# motherboard_v1.net
KiCad netlist of a schematic drawn in EAGLE
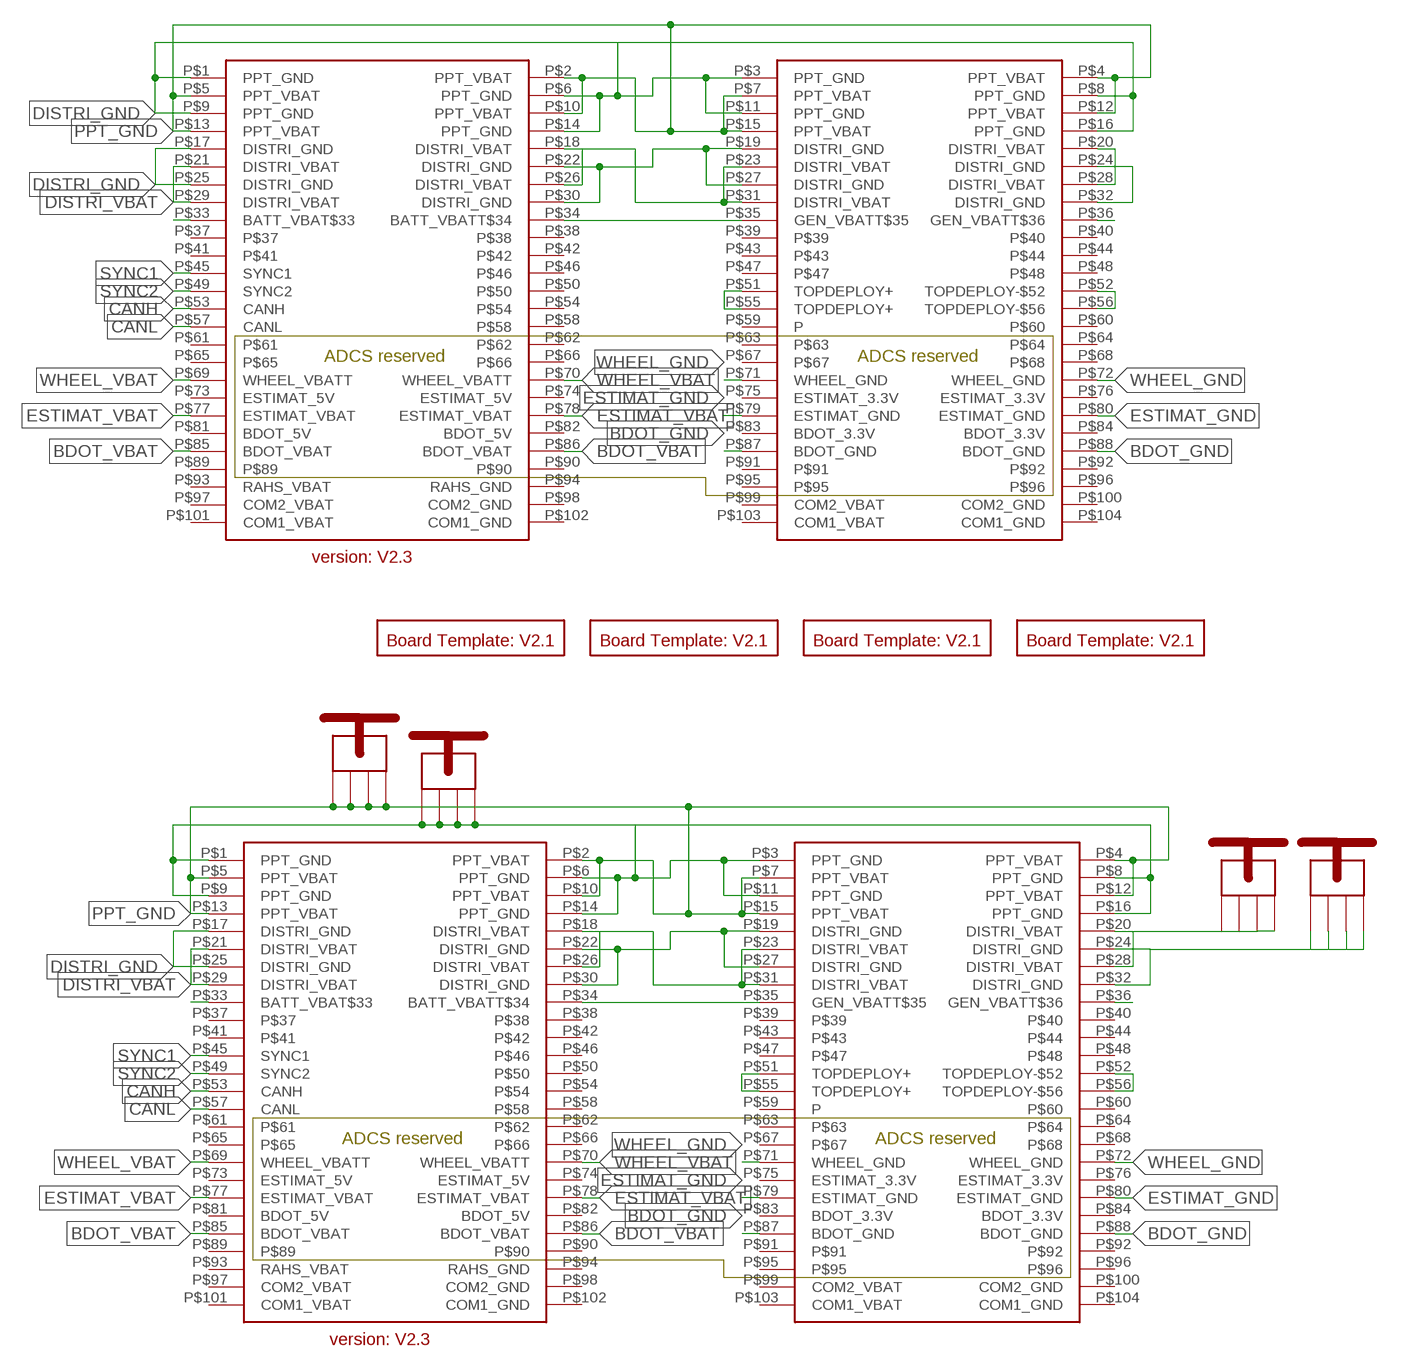
[diagram p0: schematic, sheet 1, part 1 of 2]
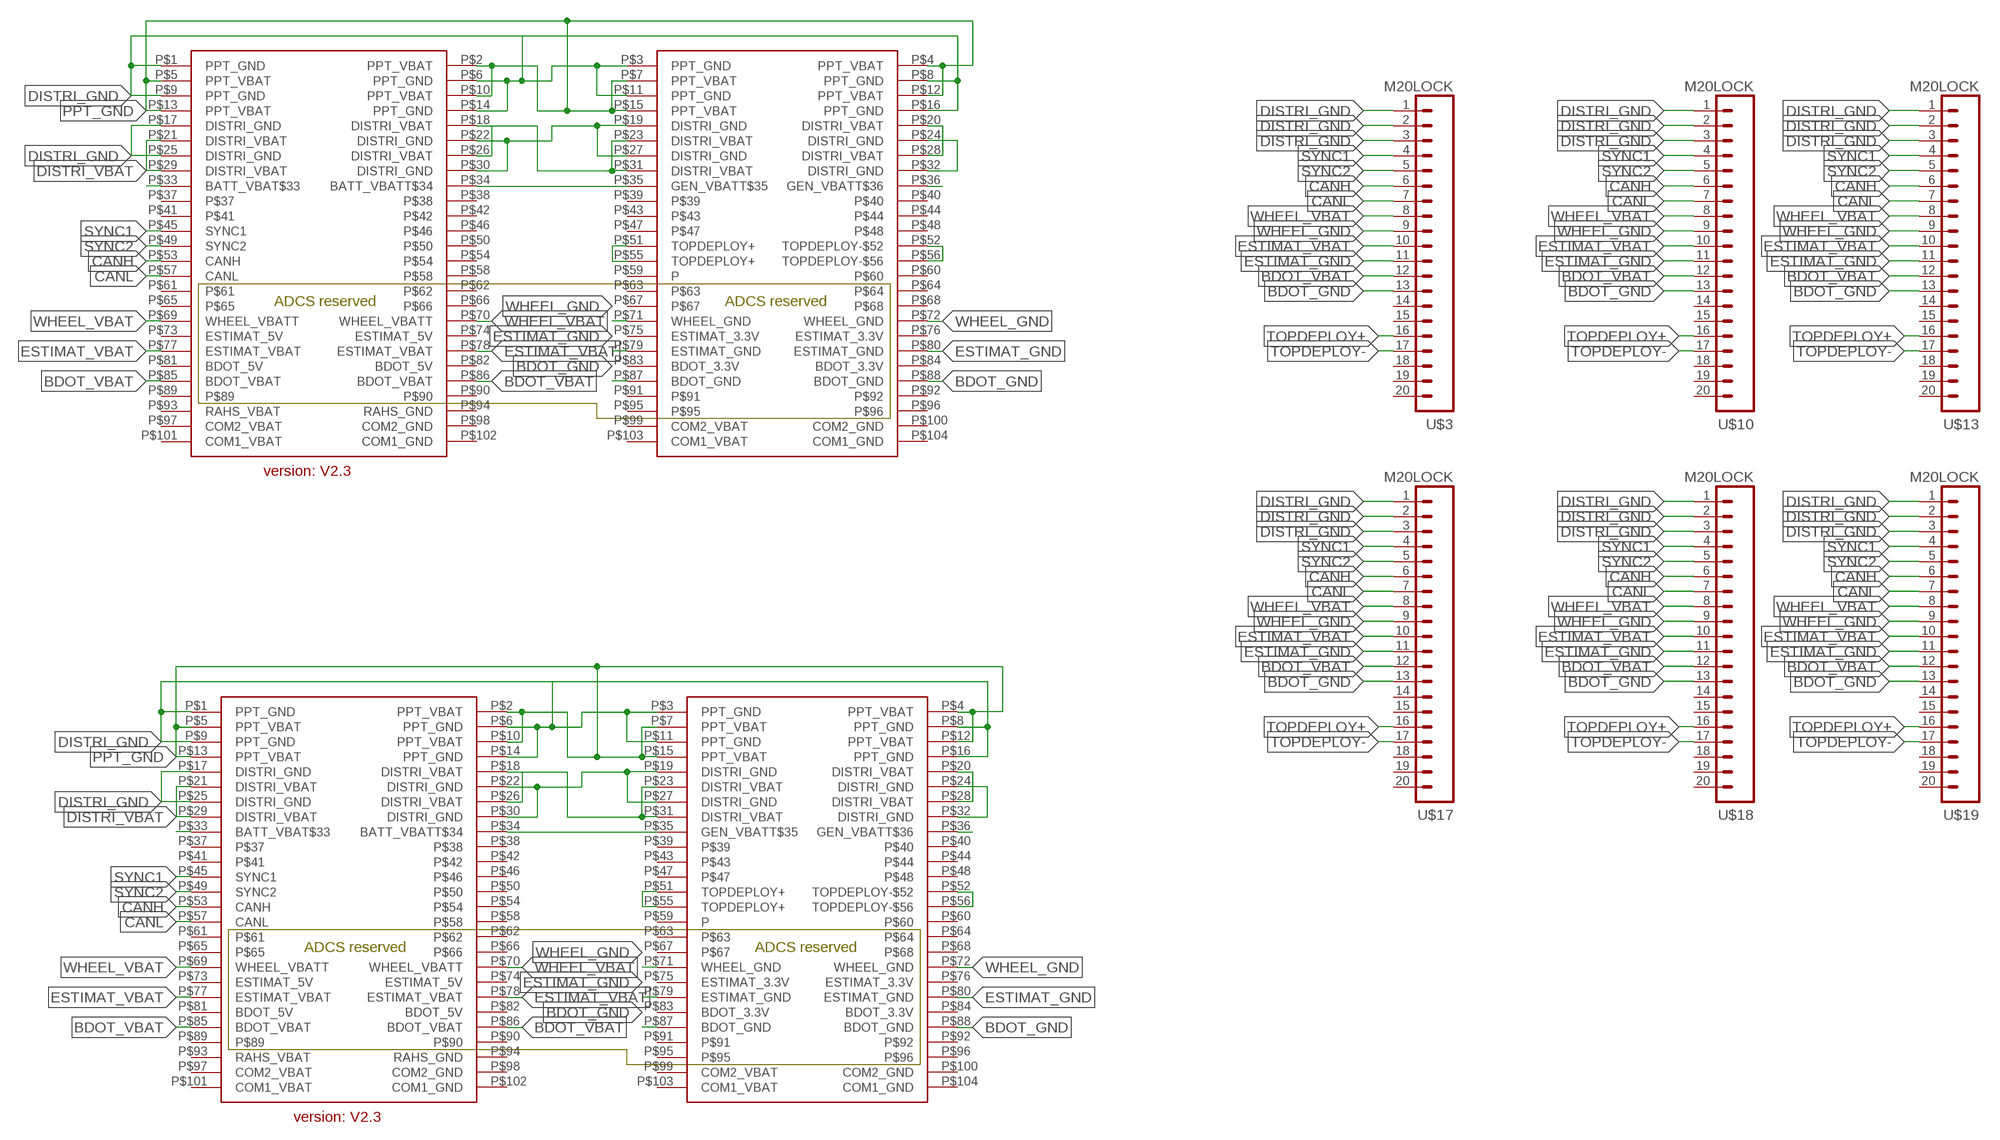
[diagram p1: schematic, sheet 1, part 2 of 2]

(export (version "E")
  (design (tool "Eeschema 10.0.6"))
  (components
    (comp (ref "JP1")
      (value "KEYSTONE_SCREW_TERMINAL_7701")
      (footprint "eagle-import:7701")
      (libsource (lib "eagle-import") (part "KEYSTONE_SCREW_TERMINAL_7701"))
    )
    (comp (ref "JP2")
      (value "KEYSTONE_SCREW_TERMINAL_7701")
      (footprint "eagle-import:7701")
      (libsource (lib "eagle-import") (part "KEYSTONE_SCREW_TERMINAL_7701"))
    )
    (comp (ref "JP9")
      (value "KEYSTONE_SCREW_TERMINAL_7701")
      (footprint "eagle-import:7701")
      (libsource (lib "eagle-import") (part "KEYSTONE_SCREW_TERMINAL_7701"))
    )
    (comp (ref "JP10")
      (value "KEYSTONE_SCREW_TERMINAL_7701")
      (footprint "eagle-import:7701")
      (libsource (lib "eagle-import") (part "KEYSTONE_SCREW_TERMINAL_7701"))
    )
    (comp (ref "U$1")
      (value "BOARD_TEMPLATESILKONLY")
      (footprint "eagle-import:BOARD_TEMPLATE_SILKONLY")
      (libsource (lib "eagle-import") (part "BOARD_TEMPLATESILKONLY"))
    )
    (comp (ref "U$2")
      (value "PC104_CONNECTOR")
      (footprint "eagle-import:PC104_CONNECTOR")
      (libsource (lib "eagle-import") (part "PC104_CONNECTOR"))
    )
    (comp (ref "U$3")
      (value "M20LOCK")
      (footprint "eagle-import:1X20_LOCK")
      (libsource (lib "eagle-import") (part "M20LOCK"))
    )
    (comp (ref "U$4")
      (value "BOARD_TEMPLATESILKONLY")
      (footprint "eagle-import:BOARD_TEMPLATE_SILKONLY")
      (libsource (lib "eagle-import") (part "BOARD_TEMPLATESILKONLY"))
    )
    (comp (ref "U$5")
      (value "BOARD_TEMPLATESILKONLY")
      (footprint "eagle-import:BOARD_TEMPLATE_SILKONLY")
      (libsource (lib "eagle-import") (part "BOARD_TEMPLATESILKONLY"))
    )
    (comp (ref "U$6")
      (value "BOARD_TEMPLATESILKONLY")
      (footprint "eagle-import:BOARD_TEMPLATE_SILKONLY")
      (libsource (lib "eagle-import") (part "BOARD_TEMPLATESILKONLY"))
    )
    (comp (ref "U$7")
      (value "PC104_CONNECTOR")
      (footprint "eagle-import:PC104_CONNECTOR")
      (libsource (lib "eagle-import") (part "PC104_CONNECTOR"))
    )
    (comp (ref "U$9")
      (value "PC104_CONNECTOR")
      (footprint "eagle-import:PC104_CONNECTOR")
      (libsource (lib "eagle-import") (part "PC104_CONNECTOR"))
    )
    (comp (ref "U$10")
      (value "M20LOCK")
      (footprint "eagle-import:1X20_LOCK")
      (libsource (lib "eagle-import") (part "M20LOCK"))
    )
    (comp (ref "U$11")
      (value "PC104_CONNECTOR")
      (footprint "eagle-import:PC104_CONNECTOR")
      (libsource (lib "eagle-import") (part "PC104_CONNECTOR"))
    )
    (comp (ref "U$13")
      (value "M20LOCK")
      (footprint "eagle-import:1X20_LOCK")
      (libsource (lib "eagle-import") (part "M20LOCK"))
    )
    (comp (ref "U$17")
      (value "M20LOCK")
      (footprint "eagle-import:1X20_LOCK")
      (libsource (lib "eagle-import") (part "M20LOCK"))
    )
    (comp (ref "U$18")
      (value "M20LOCK")
      (footprint "eagle-import:1X20_LOCK")
      (libsource (lib "eagle-import") (part "M20LOCK"))
    )
    (comp (ref "U$19")
      (value "M20LOCK")
      (footprint "eagle-import:1X20_LOCK")
      (libsource (lib "eagle-import") (part "M20LOCK"))
    )
  )
  (nets
    (net (code "1") (name "/EPS") (class "Default")
      (node (ref "U$11") (pin "P$33") (pinfunction "BATT_VBAT$33_P$33") (pintype "bidirectional"))
      (node (ref "U$11") (pin "P$34") (pinfunction "BATT_VBATT$34_P$34") (pintype "bidirectional"))
      (node (ref "U$11") (pin "P$35") (pinfunction "GEN_VBATT$35_P$35") (pintype "bidirectional"))
      (node (ref "U$11") (pin "P$36") (pinfunction "GEN_VBATT$36_P$36") (pintype "bidirectional"))
      (node (ref "U$2") (pin "P$33") (pinfunction "BATT_VBAT$33_P$33") (pintype "bidirectional"))
      (node (ref "U$2") (pin "P$34") (pinfunction "BATT_VBATT$34_P$34") (pintype "bidirectional"))
      (node (ref "U$2") (pin "P$35") (pinfunction "GEN_VBATT$35_P$35") (pintype "bidirectional"))
      (node (ref "U$2") (pin "P$36") (pinfunction "GEN_VBATT$36_P$36") (pintype "bidirectional"))
      (node (ref "U$7") (pin "P$33") (pinfunction "BATT_VBAT$33_P$33") (pintype "bidirectional"))
      (node (ref "U$7") (pin "P$34") (pinfunction "BATT_VBATT$34_P$34") (pintype "bidirectional"))
      (node (ref "U$7") (pin "P$35") (pinfunction "GEN_VBATT$35_P$35") (pintype "bidirectional"))
      (node (ref "U$7") (pin "P$36") (pinfunction "GEN_VBATT$36_P$36") (pintype "bidirectional"))
      (node (ref "U$9") (pin "P$33") (pinfunction "BATT_VBAT$33_P$33") (pintype "bidirectional"))
      (node (ref "U$9") (pin "P$34") (pinfunction "BATT_VBATT$34_P$34") (pintype "bidirectional"))
      (node (ref "U$9") (pin "P$35") (pinfunction "GEN_VBATT$35_P$35") (pintype "bidirectional"))
      (node (ref "U$9") (pin "P$36") (pinfunction "GEN_VBATT$36_P$36") (pintype "bidirectional"))
    )
    (net (code "2") (name "BDOT_GND") (class "Default")
      (node (ref "U$10") (pin "13") (pinfunction "13_13") (pintype "passive"))
      (node (ref "U$11") (pin "P$87") (pinfunction "BDOT_GND_P$87") (pintype "bidirectional"))
      (node (ref "U$11") (pin "P$88") (pinfunction "BDOT_GND_P$88") (pintype "bidirectional"))
      (node (ref "U$13") (pin "13") (pinfunction "13_13") (pintype "passive"))
      (node (ref "U$17") (pin "13") (pinfunction "13_13") (pintype "passive"))
      (node (ref "U$18") (pin "13") (pinfunction "13_13") (pintype "passive"))
      (node (ref "U$19") (pin "13") (pinfunction "13_13") (pintype "passive"))
      (node (ref "U$2") (pin "P$87") (pinfunction "BDOT_GND_P$87") (pintype "bidirectional"))
      (node (ref "U$2") (pin "P$88") (pinfunction "BDOT_GND_P$88") (pintype "bidirectional"))
      (node (ref "U$3") (pin "13") (pinfunction "13_13") (pintype "passive"))
      (node (ref "U$7") (pin "P$87") (pinfunction "BDOT_GND_P$87") (pintype "bidirectional"))
      (node (ref "U$7") (pin "P$88") (pinfunction "BDOT_GND_P$88") (pintype "bidirectional"))
      (node (ref "U$9") (pin "P$87") (pinfunction "BDOT_GND_P$87") (pintype "bidirectional"))
      (node (ref "U$9") (pin "P$88") (pinfunction "BDOT_GND_P$88") (pintype "bidirectional"))
    )
    (net (code "3") (name "BDOT_VBAT") (class "Default")
      (node (ref "U$10") (pin "12") (pinfunction "12_12") (pintype "passive"))
      (node (ref "U$11") (pin "P$85") (pinfunction "BDOT_VBAT_P$85") (pintype "bidirectional"))
      (node (ref "U$11") (pin "P$86") (pinfunction "BDOT_VBAT_P$86") (pintype "bidirectional"))
      (node (ref "U$13") (pin "12") (pinfunction "12_12") (pintype "passive"))
      (node (ref "U$17") (pin "12") (pinfunction "12_12") (pintype "passive"))
      (node (ref "U$18") (pin "12") (pinfunction "12_12") (pintype "passive"))
      (node (ref "U$19") (pin "12") (pinfunction "12_12") (pintype "passive"))
      (node (ref "U$2") (pin "P$85") (pinfunction "BDOT_VBAT_P$85") (pintype "bidirectional"))
      (node (ref "U$2") (pin "P$86") (pinfunction "BDOT_VBAT_P$86") (pintype "bidirectional"))
      (node (ref "U$3") (pin "12") (pinfunction "12_12") (pintype "passive"))
      (node (ref "U$7") (pin "P$85") (pinfunction "BDOT_VBAT_P$85") (pintype "bidirectional"))
      (node (ref "U$7") (pin "P$86") (pinfunction "BDOT_VBAT_P$86") (pintype "bidirectional"))
      (node (ref "U$9") (pin "P$85") (pinfunction "BDOT_VBAT_P$85") (pintype "bidirectional"))
      (node (ref "U$9") (pin "P$86") (pinfunction "BDOT_VBAT_P$86") (pintype "bidirectional"))
    )
    (net (code "4") (name "CANH") (class "Default")
      (node (ref "U$10") (pin "6") (pinfunction "6_6") (pintype "passive"))
      (node (ref "U$11") (pin "P$53") (pinfunction "CANH_P$53") (pintype "bidirectional"))
      (node (ref "U$13") (pin "6") (pinfunction "6_6") (pintype "passive"))
      (node (ref "U$17") (pin "6") (pinfunction "6_6") (pintype "passive"))
      (node (ref "U$18") (pin "6") (pinfunction "6_6") (pintype "passive"))
      (node (ref "U$19") (pin "6") (pinfunction "6_6") (pintype "passive"))
      (node (ref "U$2") (pin "P$53") (pinfunction "CANH_P$53") (pintype "bidirectional"))
      (node (ref "U$3") (pin "6") (pinfunction "6_6") (pintype "passive"))
      (node (ref "U$7") (pin "P$53") (pinfunction "CANH_P$53") (pintype "bidirectional"))
      (node (ref "U$9") (pin "P$53") (pinfunction "CANH_P$53") (pintype "bidirectional"))
    )
    (net (code "5") (name "CANL") (class "Default")
      (node (ref "U$10") (pin "7") (pinfunction "7_7") (pintype "passive"))
      (node (ref "U$11") (pin "P$57") (pinfunction "CANL_P$57") (pintype "bidirectional"))
      (node (ref "U$13") (pin "7") (pinfunction "7_7") (pintype "passive"))
      (node (ref "U$17") (pin "7") (pinfunction "7_7") (pintype "passive"))
      (node (ref "U$18") (pin "7") (pinfunction "7_7") (pintype "passive"))
      (node (ref "U$19") (pin "7") (pinfunction "7_7") (pintype "passive"))
      (node (ref "U$2") (pin "P$57") (pinfunction "CANL_P$57") (pintype "bidirectional"))
      (node (ref "U$3") (pin "7") (pinfunction "7_7") (pintype "passive"))
      (node (ref "U$7") (pin "P$57") (pinfunction "CANL_P$57") (pintype "bidirectional"))
      (node (ref "U$9") (pin "P$57") (pinfunction "CANL_P$57") (pintype "bidirectional"))
    )
    (net (code "6") (name "DISTRI_GND") (class "Default")
      (node (ref "JP10") (pin "P$1") (pinfunction "P$1_P$1") (pintype "bidirectional"))
      (node (ref "JP10") (pin "P$2") (pinfunction "P$2_P$2") (pintype "bidirectional"))
      (node (ref "JP10") (pin "P$3") (pinfunction "P$3_P$3") (pintype "bidirectional"))
      (node (ref "JP10") (pin "P$4") (pinfunction "P$4_P$4") (pintype "bidirectional"))
      (node (ref "JP2") (pin "P$1") (pinfunction "P$1_P$1") (pintype "bidirectional"))
      (node (ref "JP2") (pin "P$2") (pinfunction "P$2_P$2") (pintype "bidirectional"))
      (node (ref "JP2") (pin "P$3") (pinfunction "P$3_P$3") (pintype "bidirectional"))
      (node (ref "JP2") (pin "P$4") (pinfunction "P$4_P$4") (pintype "bidirectional"))
      (node (ref "U$10") (pin "1") (pinfunction "1_1") (pintype "passive"))
      (node (ref "U$10") (pin "2") (pinfunction "2_2") (pintype "passive"))
      (node (ref "U$10") (pin "3") (pinfunction "3_3") (pintype "passive"))
      (node (ref "U$11") (pin "P$1") (pinfunction "PPT_GND_P$1") (pintype "bidirectional"))
      (node (ref "U$11") (pin "P$11") (pinfunction "PPT_GND_P$11") (pintype "bidirectional"))
      (node (ref "U$11") (pin "P$14") (pinfunction "PPT_GND_P$14") (pintype "bidirectional"))
      (node (ref "U$11") (pin "P$16") (pinfunction "PPT_GND_P$16") (pintype "bidirectional"))
      (node (ref "U$11") (pin "P$17") (pinfunction "DISTRI_GND_P$17") (pintype "bidirectional"))
      (node (ref "U$11") (pin "P$19") (pinfunction "DISTRI_GND_P$19") (pintype "bidirectional"))
      (node (ref "U$11") (pin "P$22") (pinfunction "DISTRI_GND_P$22") (pintype "bidirectional"))
      (node (ref "U$11") (pin "P$24") (pinfunction "DISTRI_GND_P$24") (pintype "bidirectional"))
      (node (ref "U$11") (pin "P$25") (pinfunction "DISTRI_GND_P$25") (pintype "bidirectional"))
      (node (ref "U$11") (pin "P$27") (pinfunction "DISTRI_GND_P$27") (pintype "bidirectional"))
      (node (ref "U$11") (pin "P$3") (pinfunction "PPT_GND_P$3") (pintype "bidirectional"))
      (node (ref "U$11") (pin "P$30") (pinfunction "DISTRI_GND_P$30") (pintype "bidirectional"))
      (node (ref "U$11") (pin "P$32") (pinfunction "DISTRI_GND_P$32") (pintype "bidirectional"))
      (node (ref "U$11") (pin "P$6") (pinfunction "PPT_GND_P$6") (pintype "bidirectional"))
      (node (ref "U$11") (pin "P$8") (pinfunction "PPT_GND_P$8") (pintype "bidirectional"))
      (node (ref "U$11") (pin "P$9") (pinfunction "PPT_GND_P$9") (pintype "bidirectional"))
      (node (ref "U$13") (pin "1") (pinfunction "1_1") (pintype "passive"))
      (node (ref "U$13") (pin "2") (pinfunction "2_2") (pintype "passive"))
      (node (ref "U$13") (pin "3") (pinfunction "3_3") (pintype "passive"))
      (node (ref "U$17") (pin "1") (pinfunction "1_1") (pintype "passive"))
      (node (ref "U$17") (pin "2") (pinfunction "2_2") (pintype "passive"))
      (node (ref "U$17") (pin "3") (pinfunction "3_3") (pintype "passive"))
      (node (ref "U$18") (pin "1") (pinfunction "1_1") (pintype "passive"))
      (node (ref "U$18") (pin "2") (pinfunction "2_2") (pintype "passive"))
      (node (ref "U$18") (pin "3") (pinfunction "3_3") (pintype "passive"))
      (node (ref "U$19") (pin "1") (pinfunction "1_1") (pintype "passive"))
      (node (ref "U$19") (pin "2") (pinfunction "2_2") (pintype "passive"))
      (node (ref "U$19") (pin "3") (pinfunction "3_3") (pintype "passive"))
      (node (ref "U$2") (pin "P$1") (pinfunction "PPT_GND_P$1") (pintype "bidirectional"))
      (node (ref "U$2") (pin "P$11") (pinfunction "PPT_GND_P$11") (pintype "bidirectional"))
      (node (ref "U$2") (pin "P$14") (pinfunction "PPT_GND_P$14") (pintype "bidirectional"))
      (node (ref "U$2") (pin "P$16") (pinfunction "PPT_GND_P$16") (pintype "bidirectional"))
      (node (ref "U$2") (pin "P$17") (pinfunction "DISTRI_GND_P$17") (pintype "bidirectional"))
      (node (ref "U$2") (pin "P$19") (pinfunction "DISTRI_GND_P$19") (pintype "bidirectional"))
      (node (ref "U$2") (pin "P$22") (pinfunction "DISTRI_GND_P$22") (pintype "bidirectional"))
      (node (ref "U$2") (pin "P$24") (pinfunction "DISTRI_GND_P$24") (pintype "bidirectional"))
      (node (ref "U$2") (pin "P$25") (pinfunction "DISTRI_GND_P$25") (pintype "bidirectional"))
      (node (ref "U$2") (pin "P$27") (pinfunction "DISTRI_GND_P$27") (pintype "bidirectional"))
      (node (ref "U$2") (pin "P$3") (pinfunction "PPT_GND_P$3") (pintype "bidirectional"))
      (node (ref "U$2") (pin "P$30") (pinfunction "DISTRI_GND_P$30") (pintype "bidirectional"))
      (node (ref "U$2") (pin "P$32") (pinfunction "DISTRI_GND_P$32") (pintype "bidirectional"))
      (node (ref "U$2") (pin "P$6") (pinfunction "PPT_GND_P$6") (pintype "bidirectional"))
      (node (ref "U$2") (pin "P$8") (pinfunction "PPT_GND_P$8") (pintype "bidirectional"))
      (node (ref "U$2") (pin "P$9") (pinfunction "PPT_GND_P$9") (pintype "bidirectional"))
      (node (ref "U$3") (pin "1") (pinfunction "1_1") (pintype "passive"))
      (node (ref "U$3") (pin "2") (pinfunction "2_2") (pintype "passive"))
      (node (ref "U$3") (pin "3") (pinfunction "3_3") (pintype "passive"))
      (node (ref "U$7") (pin "P$1") (pinfunction "PPT_GND_P$1") (pintype "bidirectional"))
      (node (ref "U$7") (pin "P$11") (pinfunction "PPT_GND_P$11") (pintype "bidirectional"))
      (node (ref "U$7") (pin "P$14") (pinfunction "PPT_GND_P$14") (pintype "bidirectional"))
      (node (ref "U$7") (pin "P$16") (pinfunction "PPT_GND_P$16") (pintype "bidirectional"))
      (node (ref "U$7") (pin "P$17") (pinfunction "DISTRI_GND_P$17") (pintype "bidirectional"))
      (node (ref "U$7") (pin "P$19") (pinfunction "DISTRI_GND_P$19") (pintype "bidirectional"))
      (node (ref "U$7") (pin "P$22") (pinfunction "DISTRI_GND_P$22") (pintype "bidirectional"))
      (node (ref "U$7") (pin "P$24") (pinfunction "DISTRI_GND_P$24") (pintype "bidirectional"))
      (node (ref "U$7") (pin "P$25") (pinfunction "DISTRI_GND_P$25") (pintype "bidirectional"))
      (node (ref "U$7") (pin "P$27") (pinfunction "DISTRI_GND_P$27") (pintype "bidirectional"))
      (node (ref "U$7") (pin "P$3") (pinfunction "PPT_GND_P$3") (pintype "bidirectional"))
      (node (ref "U$7") (pin "P$30") (pinfunction "DISTRI_GND_P$30") (pintype "bidirectional"))
      (node (ref "U$7") (pin "P$32") (pinfunction "DISTRI_GND_P$32") (pintype "bidirectional"))
      (node (ref "U$7") (pin "P$6") (pinfunction "PPT_GND_P$6") (pintype "bidirectional"))
      (node (ref "U$7") (pin "P$8") (pinfunction "PPT_GND_P$8") (pintype "bidirectional"))
      (node (ref "U$7") (pin "P$9") (pinfunction "PPT_GND_P$9") (pintype "bidirectional"))
      (node (ref "U$9") (pin "P$1") (pinfunction "PPT_GND_P$1") (pintype "bidirectional"))
      (node (ref "U$9") (pin "P$11") (pinfunction "PPT_GND_P$11") (pintype "bidirectional"))
      (node (ref "U$9") (pin "P$14") (pinfunction "PPT_GND_P$14") (pintype "bidirectional"))
      (node (ref "U$9") (pin "P$16") (pinfunction "PPT_GND_P$16") (pintype "bidirectional"))
      (node (ref "U$9") (pin "P$17") (pinfunction "DISTRI_GND_P$17") (pintype "bidirectional"))
      (node (ref "U$9") (pin "P$19") (pinfunction "DISTRI_GND_P$19") (pintype "bidirectional"))
      (node (ref "U$9") (pin "P$22") (pinfunction "DISTRI_GND_P$22") (pintype "bidirectional"))
      (node (ref "U$9") (pin "P$24") (pinfunction "DISTRI_GND_P$24") (pintype "bidirectional"))
      (node (ref "U$9") (pin "P$25") (pinfunction "DISTRI_GND_P$25") (pintype "bidirectional"))
      (node (ref "U$9") (pin "P$27") (pinfunction "DISTRI_GND_P$27") (pintype "bidirectional"))
      (node (ref "U$9") (pin "P$3") (pinfunction "PPT_GND_P$3") (pintype "bidirectional"))
      (node (ref "U$9") (pin "P$30") (pinfunction "DISTRI_GND_P$30") (pintype "bidirectional"))
      (node (ref "U$9") (pin "P$32") (pinfunction "DISTRI_GND_P$32") (pintype "bidirectional"))
      (node (ref "U$9") (pin "P$6") (pinfunction "PPT_GND_P$6") (pintype "bidirectional"))
      (node (ref "U$9") (pin "P$8") (pinfunction "PPT_GND_P$8") (pintype "bidirectional"))
      (node (ref "U$9") (pin "P$9") (pinfunction "PPT_GND_P$9") (pintype "bidirectional"))
    )
    (net (code "7") (name "DISTRI_VBAT") (class "Default")
      (node (ref "JP1") (pin "P$1") (pinfunction "P$1_P$1") (pintype "bidirectional"))
      (node (ref "JP1") (pin "P$2") (pinfunction "P$2_P$2") (pintype "bidirectional"))
      (node (ref "JP1") (pin "P$3") (pinfunction "P$3_P$3") (pintype "bidirectional"))
      (node (ref "JP1") (pin "P$4") (pinfunction "P$4_P$4") (pintype "bidirectional"))
      (node (ref "U$11") (pin "P$18") (pinfunction "DISTRI_VBAT_P$18") (pintype "bidirectional"))
      (node (ref "U$11") (pin "P$20") (pinfunction "DISTRI_VBAT_P$20") (pintype "bidirectional"))
      (node (ref "U$11") (pin "P$21") (pinfunction "DISTRI_VBAT_P$21") (pintype "bidirectional"))
      (node (ref "U$11") (pin "P$23") (pinfunction "DISTRI_VBAT_P$23") (pintype "bidirectional"))
      (node (ref "U$11") (pin "P$26") (pinfunction "DISTRI_VBAT_P$26") (pintype "bidirectional"))
      (node (ref "U$11") (pin "P$28") (pinfunction "DISTRI_VBAT_P$28") (pintype "bidirectional"))
      (node (ref "U$11") (pin "P$29") (pinfunction "DISTRI_VBAT_P$29") (pintype "bidirectional"))
      (node (ref "U$11") (pin "P$31") (pinfunction "DISTRI_VBAT_P$31") (pintype "bidirectional"))
      (node (ref "U$2") (pin "P$18") (pinfunction "DISTRI_VBAT_P$18") (pintype "bidirectional"))
      (node (ref "U$2") (pin "P$20") (pinfunction "DISTRI_VBAT_P$20") (pintype "bidirectional"))
      (node (ref "U$2") (pin "P$21") (pinfunction "DISTRI_VBAT_P$21") (pintype "bidirectional"))
      (node (ref "U$2") (pin "P$23") (pinfunction "DISTRI_VBAT_P$23") (pintype "bidirectional"))
      (node (ref "U$2") (pin "P$26") (pinfunction "DISTRI_VBAT_P$26") (pintype "bidirectional"))
      (node (ref "U$2") (pin "P$28") (pinfunction "DISTRI_VBAT_P$28") (pintype "bidirectional"))
      (node (ref "U$2") (pin "P$29") (pinfunction "DISTRI_VBAT_P$29") (pintype "bidirectional"))
      (node (ref "U$2") (pin "P$31") (pinfunction "DISTRI_VBAT_P$31") (pintype "bidirectional"))
      (node (ref "U$7") (pin "P$18") (pinfunction "DISTRI_VBAT_P$18") (pintype "bidirectional"))
      (node (ref "U$7") (pin "P$20") (pinfunction "DISTRI_VBAT_P$20") (pintype "bidirectional"))
      (node (ref "U$7") (pin "P$21") (pinfunction "DISTRI_VBAT_P$21") (pintype "bidirectional"))
      (node (ref "U$7") (pin "P$23") (pinfunction "DISTRI_VBAT_P$23") (pintype "bidirectional"))
      (node (ref "U$7") (pin "P$26") (pinfunction "DISTRI_VBAT_P$26") (pintype "bidirectional"))
      (node (ref "U$7") (pin "P$28") (pinfunction "DISTRI_VBAT_P$28") (pintype "bidirectional"))
      (node (ref "U$7") (pin "P$29") (pinfunction "DISTRI_VBAT_P$29") (pintype "bidirectional"))
      (node (ref "U$7") (pin "P$31") (pinfunction "DISTRI_VBAT_P$31") (pintype "bidirectional"))
      (node (ref "U$9") (pin "P$18") (pinfunction "DISTRI_VBAT_P$18") (pintype "bidirectional"))
      (node (ref "U$9") (pin "P$20") (pinfunction "DISTRI_VBAT_P$20") (pintype "bidirectional"))
      (node (ref "U$9") (pin "P$21") (pinfunction "DISTRI_VBAT_P$21") (pintype "bidirectional"))
      (node (ref "U$9") (pin "P$23") (pinfunction "DISTRI_VBAT_P$23") (pintype "bidirectional"))
      (node (ref "U$9") (pin "P$26") (pinfunction "DISTRI_VBAT_P$26") (pintype "bidirectional"))
      (node (ref "U$9") (pin "P$28") (pinfunction "DISTRI_VBAT_P$28") (pintype "bidirectional"))
      (node (ref "U$9") (pin "P$29") (pinfunction "DISTRI_VBAT_P$29") (pintype "bidirectional"))
      (node (ref "U$9") (pin "P$31") (pinfunction "DISTRI_VBAT_P$31") (pintype "bidirectional"))
    )
    (net (code "8") (name "ESTIMAT_GND") (class "Default")
      (node (ref "U$10") (pin "11") (pinfunction "11_11") (pintype "passive"))
      (node (ref "U$11") (pin "P$79") (pinfunction "ESTIMAT_GND_P$79") (pintype "bidirectional"))
      (node (ref "U$11") (pin "P$80") (pinfunction "ESTIMAT_GND_P$80") (pintype "bidirectional"))
      (node (ref "U$13") (pin "11") (pinfunction "11_11") (pintype "passive"))
      (node (ref "U$17") (pin "11") (pinfunction "11_11") (pintype "passive"))
      (node (ref "U$18") (pin "11") (pinfunction "11_11") (pintype "passive"))
      (node (ref "U$19") (pin "11") (pinfunction "11_11") (pintype "passive"))
      (node (ref "U$2") (pin "P$79") (pinfunction "ESTIMAT_GND_P$79") (pintype "bidirectional"))
      (node (ref "U$2") (pin "P$80") (pinfunction "ESTIMAT_GND_P$80") (pintype "bidirectional"))
      (node (ref "U$3") (pin "11") (pinfunction "11_11") (pintype "passive"))
      (node (ref "U$7") (pin "P$79") (pinfunction "ESTIMAT_GND_P$79") (pintype "bidirectional"))
      (node (ref "U$7") (pin "P$80") (pinfunction "ESTIMAT_GND_P$80") (pintype "bidirectional"))
      (node (ref "U$9") (pin "P$79") (pinfunction "ESTIMAT_GND_P$79") (pintype "bidirectional"))
      (node (ref "U$9") (pin "P$80") (pinfunction "ESTIMAT_GND_P$80") (pintype "bidirectional"))
    )
    (net (code "9") (name "ESTIMAT_VBAT") (class "Default")
      (node (ref "U$10") (pin "10") (pinfunction "10_10") (pintype "passive"))
      (node (ref "U$11") (pin "P$77") (pinfunction "ESTIMAT_VBAT_P$77") (pintype "bidirectional"))
      (node (ref "U$11") (pin "P$78") (pinfunction "ESTIMAT_VBAT_P$78") (pintype "bidirectional"))
      (node (ref "U$13") (pin "10") (pinfunction "10_10") (pintype "passive"))
      (node (ref "U$17") (pin "10") (pinfunction "10_10") (pintype "passive"))
      (node (ref "U$18") (pin "10") (pinfunction "10_10") (pintype "passive"))
      (node (ref "U$19") (pin "10") (pinfunction "10_10") (pintype "passive"))
      (node (ref "U$2") (pin "P$77") (pinfunction "ESTIMAT_VBAT_P$77") (pintype "bidirectional"))
      (node (ref "U$2") (pin "P$78") (pinfunction "ESTIMAT_VBAT_P$78") (pintype "bidirectional"))
      (node (ref "U$3") (pin "10") (pinfunction "10_10") (pintype "passive"))
      (node (ref "U$7") (pin "P$77") (pinfunction "ESTIMAT_VBAT_P$77") (pintype "bidirectional"))
      (node (ref "U$7") (pin "P$78") (pinfunction "ESTIMAT_VBAT_P$78") (pintype "bidirectional"))
      (node (ref "U$9") (pin "P$77") (pinfunction "ESTIMAT_VBAT_P$77") (pintype "bidirectional"))
      (node (ref "U$9") (pin "P$78") (pinfunction "ESTIMAT_VBAT_P$78") (pintype "bidirectional"))
    )
    (net (code "10") (name "PPT_GND") (class "Default")
      (node (ref "JP9") (pin "P$1") (pinfunction "P$1_P$1") (pintype "bidirectional"))
      (node (ref "JP9") (pin "P$2") (pinfunction "P$2_P$2") (pintype "bidirectional"))
      (node (ref "JP9") (pin "P$3") (pinfunction "P$3_P$3") (pintype "bidirectional"))
      (node (ref "JP9") (pin "P$4") (pinfunction "P$4_P$4") (pintype "bidirectional"))
      (node (ref "U$11") (pin "P$10") (pinfunction "PPT_VBAT_P$10") (pintype "bidirectional"))
      (node (ref "U$11") (pin "P$12") (pinfunction "PPT_VBAT_P$12") (pintype "bidirectional"))
      (node (ref "U$11") (pin "P$13") (pinfunction "PPT_VBAT_P$13") (pintype "bidirectional"))
      (node (ref "U$11") (pin "P$15") (pinfunction "PPT_VBAT_P$15") (pintype "bidirectional"))
      (node (ref "U$11") (pin "P$2") (pinfunction "PPT_VBAT_P$2") (pintype "bidirectional"))
      (node (ref "U$11") (pin "P$4") (pinfunction "PPT_VBAT_P$4") (pintype "bidirectional"))
      (node (ref "U$11") (pin "P$5") (pinfunction "PPT_VBAT_P$5") (pintype "bidirectional"))
      (node (ref "U$11") (pin "P$7") (pinfunction "PPT_VBAT_P$7") (pintype "bidirectional"))
      (node (ref "U$2") (pin "P$10") (pinfunction "PPT_VBAT_P$10") (pintype "bidirectional"))
      (node (ref "U$2") (pin "P$12") (pinfunction "PPT_VBAT_P$12") (pintype "bidirectional"))
      (node (ref "U$2") (pin "P$13") (pinfunction "PPT_VBAT_P$13") (pintype "bidirectional"))
      (node (ref "U$2") (pin "P$15") (pinfunction "PPT_VBAT_P$15") (pintype "bidirectional"))
      (node (ref "U$2") (pin "P$2") (pinfunction "PPT_VBAT_P$2") (pintype "bidirectional"))
      (node (ref "U$2") (pin "P$4") (pinfunction "PPT_VBAT_P$4") (pintype "bidirectional"))
      (node (ref "U$2") (pin "P$5") (pinfunction "PPT_VBAT_P$5") (pintype "bidirectional"))
      (node (ref "U$2") (pin "P$7") (pinfunction "PPT_VBAT_P$7") (pintype "bidirectional"))
      (node (ref "U$7") (pin "P$10") (pinfunction "PPT_VBAT_P$10") (pintype "bidirectional"))
      (node (ref "U$7") (pin "P$12") (pinfunction "PPT_VBAT_P$12") (pintype "bidirectional"))
      (node (ref "U$7") (pin "P$13") (pinfunction "PPT_VBAT_P$13") (pintype "bidirectional"))
      (node (ref "U$7") (pin "P$15") (pinfunction "PPT_VBAT_P$15") (pintype "bidirectional"))
      (node (ref "U$7") (pin "P$2") (pinfunction "PPT_VBAT_P$2") (pintype "bidirectional"))
      (node (ref "U$7") (pin "P$4") (pinfunction "PPT_VBAT_P$4") (pintype "bidirectional"))
      (node (ref "U$7") (pin "P$5") (pinfunction "PPT_VBAT_P$5") (pintype "bidirectional"))
      (node (ref "U$7") (pin "P$7") (pinfunction "PPT_VBAT_P$7") (pintype "bidirectional"))
      (node (ref "U$9") (pin "P$10") (pinfunction "PPT_VBAT_P$10") (pintype "bidirectional"))
      (node (ref "U$9") (pin "P$12") (pinfunction "PPT_VBAT_P$12") (pintype "bidirectional"))
      (node (ref "U$9") (pin "P$13") (pinfunction "PPT_VBAT_P$13") (pintype "bidirectional"))
      (node (ref "U$9") (pin "P$15") (pinfunction "PPT_VBAT_P$15") (pintype "bidirectional"))
      (node (ref "U$9") (pin "P$2") (pinfunction "PPT_VBAT_P$2") (pintype "bidirectional"))
      (node (ref "U$9") (pin "P$4") (pinfunction "PPT_VBAT_P$4") (pintype "bidirectional"))
      (node (ref "U$9") (pin "P$5") (pinfunction "PPT_VBAT_P$5") (pintype "bidirectional"))
      (node (ref "U$9") (pin "P$7") (pinfunction "PPT_VBAT_P$7") (pintype "bidirectional"))
    )
    (net (code "11") (name "SYNC1") (class "Default")
      (node (ref "U$10") (pin "4") (pinfunction "4_4") (pintype "passive"))
      (node (ref "U$11") (pin "P$45") (pinfunction "SYNC1_P$45") (pintype "bidirectional"))
      (node (ref "U$13") (pin "4") (pinfunction "4_4") (pintype "passive"))
      (node (ref "U$17") (pin "4") (pinfunction "4_4") (pintype "passive"))
      (node (ref "U$18") (pin "4") (pinfunction "4_4") (pintype "passive"))
      (node (ref "U$19") (pin "4") (pinfunction "4_4") (pintype "passive"))
      (node (ref "U$2") (pin "P$45") (pinfunction "SYNC1_P$45") (pintype "bidirectional"))
      (node (ref "U$3") (pin "4") (pinfunction "4_4") (pintype "passive"))
      (node (ref "U$7") (pin "P$45") (pinfunction "SYNC1_P$45") (pintype "bidirectional"))
      (node (ref "U$9") (pin "P$45") (pinfunction "SYNC1_P$45") (pintype "bidirectional"))
    )
    (net (code "12") (name "SYNC2") (class "Default")
      (node (ref "U$10") (pin "5") (pinfunction "5_5") (pintype "passive"))
      (node (ref "U$11") (pin "P$49") (pinfunction "SYNC2_P$49") (pintype "bidirectional"))
      (node (ref "U$13") (pin "5") (pinfunction "5_5") (pintype "passive"))
      (node (ref "U$17") (pin "5") (pinfunction "5_5") (pintype "passive"))
      (node (ref "U$18") (pin "5") (pinfunction "5_5") (pintype "passive"))
      (node (ref "U$19") (pin "5") (pinfunction "5_5") (pintype "passive"))
      (node (ref "U$2") (pin "P$49") (pinfunction "SYNC2_P$49") (pintype "bidirectional"))
      (node (ref "U$3") (pin "5") (pinfunction "5_5") (pintype "passive"))
      (node (ref "U$7") (pin "P$49") (pinfunction "SYNC2_P$49") (pintype "bidirectional"))
      (node (ref "U$9") (pin "P$49") (pinfunction "SYNC2_P$49") (pintype "bidirectional"))
    )
    (net (code "13") (name "TOPDEPLOY+") (class "Default")
      (node (ref "U$10") (pin "16") (pinfunction "16_16") (pintype "passive"))
      (node (ref "U$11") (pin "P$51") (pinfunction "TOPDEPLOY+_P$51") (pintype "bidirectional"))
      (node (ref "U$11") (pin "P$55") (pinfunction "TOPDEPLOY+_P$55") (pintype "bidirectional"))
      (node (ref "U$13") (pin "16") (pinfunction "16_16") (pintype "passive"))
      (node (ref "U$17") (pin "16") (pinfunction "16_16") (pintype "passive"))
      (node (ref "U$18") (pin "16") (pinfunction "16_16") (pintype "passive"))
      (node (ref "U$19") (pin "16") (pinfunction "16_16") (pintype "passive"))
      (node (ref "U$2") (pin "P$51") (pinfunction "TOPDEPLOY+_P$51") (pintype "bidirectional"))
      (node (ref "U$2") (pin "P$55") (pinfunction "TOPDEPLOY+_P$55") (pintype "bidirectional"))
      (node (ref "U$3") (pin "16") (pinfunction "16_16") (pintype "passive"))
      (node (ref "U$7") (pin "P$51") (pinfunction "TOPDEPLOY+_P$51") (pintype "bidirectional"))
      (node (ref "U$7") (pin "P$55") (pinfunction "TOPDEPLOY+_P$55") (pintype "bidirectional"))
      (node (ref "U$9") (pin "P$51") (pinfunction "TOPDEPLOY+_P$51") (pintype "bidirectional"))
      (node (ref "U$9") (pin "P$55") (pinfunction "TOPDEPLOY+_P$55") (pintype "bidirectional"))
    )
    (net (code "14") (name "TOPDEPLOY-") (class "Default")
      (node (ref "U$10") (pin "17") (pinfunction "17_17") (pintype "passive"))
      (node (ref "U$11") (pin "P$52") (pinfunction "TOPDEPLOY-$52_P$52") (pintype "bidirectional"))
      (node (ref "U$11") (pin "P$56") (pinfunction "TOPDEPLOY-$56_P$56") (pintype "bidirectional"))
      (node (ref "U$13") (pin "17") (pinfunction "17_17") (pintype "passive"))
      (node (ref "U$17") (pin "17") (pinfunction "17_17") (pintype "passive"))
      (node (ref "U$18") (pin "17") (pinfunction "17_17") (pintype "passive"))
      (node (ref "U$19") (pin "17") (pinfunction "17_17") (pintype "passive"))
      (node (ref "U$2") (pin "P$52") (pinfunction "TOPDEPLOY-$52_P$52") (pintype "bidirectional"))
      (node (ref "U$2") (pin "P$56") (pinfunction "TOPDEPLOY-$56_P$56") (pintype "bidirectional"))
      (node (ref "U$3") (pin "17") (pinfunction "17_17") (pintype "passive"))
      (node (ref "U$7") (pin "P$52") (pinfunction "TOPDEPLOY-$52_P$52") (pintype "bidirectional"))
      (node (ref "U$7") (pin "P$56") (pinfunction "TOPDEPLOY-$56_P$56") (pintype "bidirectional"))
      (node (ref "U$9") (pin "P$52") (pinfunction "TOPDEPLOY-$52_P$52") (pintype "bidirectional"))
      (node (ref "U$9") (pin "P$56") (pinfunction "TOPDEPLOY-$56_P$56") (pintype "bidirectional"))
    )
    (net (code "15") (name "WHEEL_GND") (class "Default")
      (node (ref "U$10") (pin "9") (pinfunction "9_9") (pintype "passive"))
      (node (ref "U$11") (pin "P$71") (pinfunction "WHEEL_GND_P$71") (pintype "bidirectional"))
      (node (ref "U$11") (pin "P$72") (pinfunction "WHEEL_GND_P$72") (pintype "bidirectional"))
      (node (ref "U$13") (pin "9") (pinfunction "9_9") (pintype "passive"))
      (node (ref "U$17") (pin "9") (pinfunction "9_9") (pintype "passive"))
      (node (ref "U$18") (pin "9") (pinfunction "9_9") (pintype "passive"))
      (node (ref "U$19") (pin "9") (pinfunction "9_9") (pintype "passive"))
      (node (ref "U$2") (pin "P$71") (pinfunction "WHEEL_GND_P$71") (pintype "bidirectional"))
      (node (ref "U$2") (pin "P$72") (pinfunction "WHEEL_GND_P$72") (pintype "bidirectional"))
      (node (ref "U$3") (pin "9") (pinfunction "9_9") (pintype "passive"))
      (node (ref "U$7") (pin "P$71") (pinfunction "WHEEL_GND_P$71") (pintype "bidirectional"))
      (node (ref "U$7") (pin "P$72") (pinfunction "WHEEL_GND_P$72") (pintype "bidirectional"))
      (node (ref "U$9") (pin "P$71") (pinfunction "WHEEL_GND_P$71") (pintype "bidirectional"))
      (node (ref "U$9") (pin "P$72") (pinfunction "WHEEL_GND_P$72") (pintype "bidirectional"))
    )
    (net (code "16") (name "WHEEL_VBAT") (class "Default")
      (node (ref "U$10") (pin "8") (pinfunction "8_8") (pintype "passive"))
      (node (ref "U$11") (pin "P$69") (pinfunction "WHEEL_VBATT_P$69") (pintype "bidirectional"))
      (node (ref "U$11") (pin "P$70") (pinfunction "WHEEL_VBATT_P$70") (pintype "bidirectional"))
      (node (ref "U$13") (pin "8") (pinfunction "8_8") (pintype "passive"))
      (node (ref "U$17") (pin "8") (pinfunction "8_8") (pintype "passive"))
      (node (ref "U$18") (pin "8") (pinfunction "8_8") (pintype "passive"))
      (node (ref "U$19") (pin "8") (pinfunction "8_8") (pintype "passive"))
      (node (ref "U$2") (pin "P$69") (pinfunction "WHEEL_VBATT_P$69") (pintype "bidirectional"))
      (node (ref "U$2") (pin "P$70") (pinfunction "WHEEL_VBATT_P$70") (pintype "bidirectional"))
      (node (ref "U$3") (pin "8") (pinfunction "8_8") (pintype "passive"))
      (node (ref "U$7") (pin "P$69") (pinfunction "WHEEL_VBATT_P$69") (pintype "bidirectional"))
      (node (ref "U$7") (pin "P$70") (pinfunction "WHEEL_VBATT_P$70") (pintype "bidirectional"))
      (node (ref "U$9") (pin "P$69") (pinfunction "WHEEL_VBATT_P$69") (pintype "bidirectional"))
      (node (ref "U$9") (pin "P$70") (pinfunction "WHEEL_VBATT_P$70") (pintype "bidirectional"))
    )
    (net (code "17") (name "unconnected-(U$2-BDOT_3.3V-PadP$83)") (class "Default")
      (node (ref "U$2") (pin "P$83") (pinfunction "BDOT_3.3V_P$83") (pintype "bidirectional"))
    )
    (net (code "18") (name "unconnected-(U$2-BDOT_3.3V-PadP$84)") (class "Default")
      (node (ref "U$2") (pin "P$84") (pinfunction "BDOT_3.3V_P$84") (pintype "bidirectional"))
    )
    (net (code "19") (name "unconnected-(U$2-BDOT_5V-PadP$81)") (class "Default")
      (node (ref "U$2") (pin "P$81") (pinfunction "BDOT_5V_P$81") (pintype "bidirectional"))
    )
    (net (code "20") (name "unconnected-(U$2-BDOT_5V-PadP$82)") (class "Default")
      (node (ref "U$2") (pin "P$82") (pinfunction "BDOT_5V_P$82") (pintype "bidirectional"))
    )
    (net (code "21") (name "unconnected-(U$2-COM1_GND-PadP$102)") (class "Default")
      (node (ref "U$2") (pin "P$102") (pinfunction "COM1_GND_P$102") (pintype "bidirectional"))
    )
    (net (code "22") (name "unconnected-(U$2-COM1_GND-PadP$104)") (class "Default")
      (node (ref "U$2") (pin "P$104") (pinfunction "COM1_GND_P$104") (pintype "bidirectional"))
    )
    (net (code "23") (name "unconnected-(U$2-COM1_VBAT-PadP$101)") (class "Default")
      (node (ref "U$2") (pin "P$101") (pinfunction "COM1_VBAT_P$101") (pintype "bidirectional"))
    )
    (net (code "24") (name "unconnected-(U$2-COM1_VBAT-PadP$103)") (class "Default")
      (node (ref "U$2") (pin "P$103") (pinfunction "COM1_VBAT_P$103") (pintype "bidirectional"))
    )
    (net (code "25") (name "unconnected-(U$2-COM2_GND-PadP$98)") (class "Default")
      (node (ref "U$2") (pin "P$98") (pinfunction "COM2_GND_P$98") (pintype "bidirectional"))
    )
    (net (code "26") (name "unconnected-(U$2-COM2_GND-PadP$100)") (class "Default")
      (node (ref "U$2") (pin "P$100") (pinfunction "COM2_GND_P$100") (pintype "bidirectional"))
    )
    (net (code "27") (name "unconnected-(U$2-COM2_VBAT-PadP$97)") (class "Default")
      (node (ref "U$2") (pin "P$97") (pinfunction "COM2_VBAT_P$97") (pintype "bidirectional"))
    )
    (net (code "28") (name "unconnected-(U$2-COM2_VBAT-PadP$99)") (class "Default")
      (node (ref "U$2") (pin "P$99") (pinfunction "COM2_VBAT_P$99") (pintype "bidirectional"))
    )
    (net (code "29") (name "unconnected-(U$2-ESTIMAT_3.3V-PadP$75)") (class "Default")
      (node (ref "U$2") (pin "P$75") (pinfunction "ESTIMAT_3.3V_P$75") (pintype "bidirectional"))
    )
    (net (code "30") (name "unconnected-(U$2-ESTIMAT_3.3V-PadP$76)") (class "Default")
      (node (ref "U$2") (pin "P$76") (pinfunction "ESTIMAT_3.3V_P$76") (pintype "bidirectional"))
    )
    (net (code "31") (name "unconnected-(U$2-ESTIMAT_5V-PadP$73)") (class "Default")
      (node (ref "U$2") (pin "P$73") (pinfunction "ESTIMAT_5V_P$73") (pintype "bidirectional"))
    )
    (net (code "32") (name "unconnected-(U$2-ESTIMAT_5V-PadP$74)") (class "Default")
      (node (ref "U$2") (pin "P$74") (pinfunction "ESTIMAT_5V_P$74") (pintype "bidirectional"))
    )
    (net (code "33") (name "unconnected-(U$2-P-PadP$59)") (class "Default")
      (node (ref "U$2") (pin "P$59") (pinfunction "P_P$59") (pintype "bidirectional"))
    )
    (net (code "34") (name "unconnected-(U$2-PadP$37)") (class "Default")
      (node (ref "U$2") (pin "P$37") (pinfunction "P$37_P$37") (pintype "bidirectional"))
    )
    (net (code "35") (name "unconnected-(U$2-PadP$38)") (class "Default")
      (node (ref "U$2") (pin "P$38") (pinfunction "P$38_P$38") (pintype "bidirectional"))
    )
    (net (code "36") (name "unconnected-(U$2-PadP$39)") (class "Default")
      (node (ref "U$2") (pin "P$39") (pinfunction "P$39_P$39") (pintype "bidirectional"))
    )
    (net (code "37") (name "unconnected-(U$2-PadP$40)") (class "Default")
      (node (ref "U$2") (pin "P$40") (pinfunction "P$40_P$40") (pintype "bidirectional"))
    )
    (net (code "38") (name "unconnected-(U$2-PadP$41)") (class "Default")
      (node (ref "U$2") (pin "P$41") (pinfunction "P$41_P$41") (pintype "bidirectional"))
    )
    (net (code "39") (name "unconnected-(U$2-PadP$42)") (class "Default")
      (node (ref "U$2") (pin "P$42") (pinfunction "P$42_P$42") (pintype "bidirectional"))
    )
    (net (code "40") (name "unconnected-(U$2-PadP$43)") (class "Default")
      (node (ref "U$2") (pin "P$43") (pinfunction "P$43_P$43") (pintype "bidirectional"))
    )
    (net (code "41") (name "unconnected-(U$2-PadP$44)") (class "Default")
      (node (ref "U$2") (pin "P$44") (pinfunction "P$44_P$44") (pintype "bidirectional"))
    )
    (net (code "42") (name "unconnected-(U$2-PadP$46)") (class "Default")
      (node (ref "U$2") (pin "P$46") (pinfunction "P$46_P$46") (pintype "bidirectional"))
    )
    (net (code "43") (name "unconnected-(U$2-PadP$47)") (class "Default")
      (node (ref "U$2") (pin "P$47") (pinfunction "P$47_P$47") (pintype "bidirectional"))
    )
    (net (code "44") (name "unconnected-(U$2-PadP$48)") (class "Default")
      (node (ref "U$2") (pin "P$48") (pinfunction "P$48_P$48") (pintype "bidirectional"))
    )
    (net (code "45") (name "unconnected-(U$2-PadP$50)") (class "Default")
      (node (ref "U$2") (pin "P$50") (pinfunction "P$50_P$50") (pintype "bidirectional"))
    )
    (net (code "46") (name "unconnected-(U$2-PadP$54)") (class "Default")
      (node (ref "U$2") (pin "P$54") (pinfunction "P$54_P$54") (pintype "bidirectional"))
    )
    (net (code "47") (name "unconnected-(U$2-PadP$58)") (class "Default")
      (node (ref "U$2") (pin "P$58") (pinfunction "P$58_P$58") (pintype "bidirectional"))
    )
    (net (code "48") (name "unconnected-(U$2-PadP$60)") (class "Default")
      (node (ref "U$2") (pin "P$60") (pinfunction "P$60_P$60") (pintype "bidirectional"))
    )
    (net (code "49") (name "unconnected-(U$2-PadP$61)") (class "Default")
      (node (ref "U$2") (pin "P$61") (pinfunction "P$61_P$61") (pintype "bidirectional"))
    )
    (net (code "50") (name "unconnected-(U$2-PadP$62)") (class "Default")
      (node (ref "U$2") (pin "P$62") (pinfunction "P$62_P$62") (pintype "bidirectional"))
    )
    (net (code "51") (name "unconnected-(U$2-PadP$63)") (class "Default")
      (node (ref "U$2") (pin "P$63") (pinfunction "P$63_P$63") (pintype "bidirectional"))
    )
    (net (code "52") (name "unconnected-(U$2-PadP$64)") (class "Default")
      (node (ref "U$2") (pin "P$64") (pinfunction "P$64_P$64") (pintype "bidirectional"))
    )
    (net (code "53") (name "unconnected-(U$2-PadP$65)") (class "Default")
      (node (ref "U$2") (pin "P$65") (pinfunction "P$65_P$65") (pintype "bidirectional"))
    )
    (net (code "54") (name "unconnected-(U$2-PadP$66)") (class "Default")
      (node (ref "U$2") (pin "P$66") (pinfunction "P$66_P$66") (pintype "bidirectional"))
    )
    (net (code "55") (name "unconnected-(U$2-PadP$67)") (class "Default")
      (node (ref "U$2") (pin "P$67") (pinfunction "P$67_P$67") (pintype "bidirectional"))
    )
    (net (code "56") (name "unconnected-(U$2-PadP$68)") (class "Default")
      (node (ref "U$2") (pin "P$68") (pinfunction "P$68_P$68") (pintype "bidirectional"))
    )
    (net (code "57") (name "unconnected-(U$2-PadP$89)") (class "Default")
      (node (ref "U$2") (pin "P$89") (pinfunction "P$89_P$89") (pintype "bidirectional"))
    )
    (net (code "58") (name "unconnected-(U$2-PadP$90)") (class "Default")
      (node (ref "U$2") (pin "P$90") (pinfunction "P$90_P$90") (pintype "bidirectional"))
    )
    (net (code "59") (name "unconnected-(U$2-PadP$91)") (class "Default")
      (node (ref "U$2") (pin "P$91") (pinfunction "P$91_P$91") (pintype "bidirectional"))
    )
    (net (code "60") (name "unconnected-(U$2-PadP$92)") (class "Default")
      (node (ref "U$2") (pin "P$92") (pinfunction "P$92_P$92") (pintype "bidirectional"))
    )
    (net (code "61") (name "unconnected-(U$2-PadP$95)") (class "Default")
      (node (ref "U$2") (pin "P$95") (pinfunction "P$95_P$95") (pintype "bidirectional"))
    )
    (net (code "62") (name "unconnected-(U$2-PadP$96)") (class "Default")
      (node (ref "U$2") (pin "P$96") (pinfunction "P$96_P$96") (pintype "bidirectional"))
    )
    (net (code "63") (name "unconnected-(U$2-RAHS_GND-PadP$94)") (class "Default")
      (node (ref "U$2") (pin "P$94") (pinfunction "RAHS_GND_P$94") (pintype "bidirectional"))
    )
    (net (code "64") (name "unconnected-(U$2-RAHS_VBAT-PadP$93)") (class "Default")
      (node (ref "U$2") (pin "P$93") (pinfunction "RAHS_VBAT_P$93") (pintype "bidirectional"))
    )
    (net (code "65") (name "unconnected-(U$3-Pad14)") (class "Default")
      (node (ref "U$3") (pin "14") (pinfunction "14_14") (pintype "passive"))
    )
    (net (code "66") (name "unconnected-(U$3-Pad15)") (class "Default")
      (node (ref "U$3") (pin "15") (pinfunction "15_15") (pintype "passive"))
    )
    (net (code "67") (name "unconnected-(U$3-Pad18)") (class "Default")
      (node (ref "U$3") (pin "18") (pinfunction "18_18") (pintype "passive"))
    )
    (net (code "68") (name "unconnected-(U$3-Pad19)") (class "Default")
      (node (ref "U$3") (pin "19") (pinfunction "19_19") (pintype "passive"))
    )
    (net (code "69") (name "unconnected-(U$3-Pad20)") (class "Default")
      (node (ref "U$3") (pin "20") (pinfunction "20_20") (pintype "passive"))
    )
    (net (code "70") (name "unconnected-(U$7-BDOT_3.3V-PadP$83)") (class "Default")
      (node (ref "U$7") (pin "P$83") (pinfunction "BDOT_3.3V_P$83") (pintype "bidirectional"))
    )
    (net (code "71") (name "unconnected-(U$7-BDOT_3.3V-PadP$84)") (class "Default")
      (node (ref "U$7") (pin "P$84") (pinfunction "BDOT_3.3V_P$84") (pintype "bidirectional"))
    )
    (net (code "72") (name "unconnected-(U$7-BDOT_5V-PadP$81)") (class "Default")
      (node (ref "U$7") (pin "P$81") (pinfunction "BDOT_5V_P$81") (pintype "bidirectional"))
    )
    (net (code "73") (name "unconnected-(U$7-BDOT_5V-PadP$82)") (class "Default")
      (node (ref "U$7") (pin "P$82") (pinfunction "BDOT_5V_P$82") (pintype "bidirectional"))
    )
    (net (code "74") (name "unconnected-(U$7-COM1_GND-PadP$102)") (class "Default")
      (node (ref "U$7") (pin "P$102") (pinfunction "COM1_GND_P$102") (pintype "bidirectional"))
    )
    (net (code "75") (name "unconnected-(U$7-COM1_GND-PadP$104)") (class "Default")
      (node (ref "U$7") (pin "P$104") (pinfunction "COM1_GND_P$104") (pintype "bidirectional"))
    )
    (net (code "76") (name "unconnected-(U$7-COM1_VBAT-PadP$101)") (class "Default")
      (node (ref "U$7") (pin "P$101") (pinfunction "COM1_VBAT_P$101") (pintype "bidirectional"))
    )
    (net (code "77") (name "unconnected-(U$7-COM1_VBAT-PadP$103)") (class "Default")
      (node (ref "U$7") (pin "P$103") (pinfunction "COM1_VBAT_P$103") (pintype "bidirectional"))
    )
    (net (code "78") (name "unconnected-(U$7-COM2_GND-PadP$98)") (class "Default")
      (node (ref "U$7") (pin "P$98") (pinfunction "COM2_GND_P$98") (pintype "bidirectional"))
    )
    (net (code "79") (name "unconnected-(U$7-COM2_GND-PadP$100)") (class "Default")
      (node (ref "U$7") (pin "P$100") (pinfunction "COM2_GND_P$100") (pintype "bidirectional"))
    )
    (net (code "80") (name "unconnected-(U$7-COM2_VBAT-PadP$97)") (class "Default")
      (node (ref "U$7") (pin "P$97") (pinfunction "COM2_VBAT_P$97") (pintype "bidirectional"))
    )
    (net (code "81") (name "unconnected-(U$7-COM2_VBAT-PadP$99)") (class "Default")
      (node (ref "U$7") (pin "P$99") (pinfunction "COM2_VBAT_P$99") (pintype "bidirectional"))
    )
    (net (code "82") (name "unconnected-(U$7-ESTIMAT_3.3V-PadP$75)") (class "Default")
      (node (ref "U$7") (pin "P$75") (pinfunction "ESTIMAT_3.3V_P$75") (pintype "bidirectional"))
    )
    (net (code "83") (name "unconnected-(U$7-ESTIMAT_3.3V-PadP$76)") (class "Default")
      (node (ref "U$7") (pin "P$76") (pinfunction "ESTIMAT_3.3V_P$76") (pintype "bidirectional"))
    )
    (net (code "84") (name "unconnected-(U$7-ESTIMAT_5V-PadP$73)") (class "Default")
      (node (ref "U$7") (pin "P$73") (pinfunction "ESTIMAT_5V_P$73") (pintype "bidirectional"))
    )
    (net (code "85") (name "unconnected-(U$7-ESTIMAT_5V-PadP$74)") (class "Default")
      (node (ref "U$7") (pin "P$74") (pinfunction "ESTIMAT_5V_P$74") (pintype "bidirectional"))
    )
    (net (code "86") (name "unconnected-(U$7-P-PadP$59)") (class "Default")
      (node (ref "U$7") (pin "P$59") (pinfunction "P_P$59") (pintype "bidirectional"))
    )
    (net (code "87") (name "unconnected-(U$7-PadP$37)") (class "Default")
      (node (ref "U$7") (pin "P$37") (pinfunction "P$37_P$37") (pintype "bidirectional"))
    )
    (net (code "88") (name "unconnected-(U$7-PadP$38)") (class "Default")
      (node (ref "U$7") (pin "P$38") (pinfunction "P$38_P$38") (pintype "bidirectional"))
    )
    (net (code "89") (name "unconnected-(U$7-PadP$39)") (class "Default")
      (node (ref "U$7") (pin "P$39") (pinfunction "P$39_P$39") (pintype "bidirectional"))
    )
    (net (code "90") (name "unconnected-(U$7-PadP$40)") (class "Default")
      (node (ref "U$7") (pin "P$40") (pinfunction "P$40_P$40") (pintype "bidirectional"))
    )
    (net (code "91") (name "unconnected-(U$7-PadP$41)") (class "Default")
      (node (ref "U$7") (pin "P$41") (pinfunction "P$41_P$41") (pintype "bidirectional"))
    )
    (net (code "92") (name "unconnected-(U$7-PadP$42)") (class "Default")
      (node (ref "U$7") (pin "P$42") (pinfunction "P$42_P$42") (pintype "bidirectional"))
    )
    (net (code "93") (name "unconnected-(U$7-PadP$43)") (class "Default")
      (node (ref "U$7") (pin "P$43") (pinfunction "P$43_P$43") (pintype "bidirectional"))
    )
    (net (code "94") (name "unconnected-(U$7-PadP$44)") (class "Default")
      (node (ref "U$7") (pin "P$44") (pinfunction "P$44_P$44") (pintype "bidirectional"))
    )
    (net (code "95") (name "unconnected-(U$7-PadP$46)") (class "Default")
      (node (ref "U$7") (pin "P$46") (pinfunction "P$46_P$46") (pintype "bidirectional"))
    )
    (net (code "96") (name "unconnected-(U$7-PadP$47)") (class "Default")
      (node (ref "U$7") (pin "P$47") (pinfunction "P$47_P$47") (pintype "bidirectional"))
    )
    (net (code "97") (name "unconnected-(U$7-PadP$48)") (class "Default")
      (node (ref "U$7") (pin "P$48") (pinfunction "P$48_P$48") (pintype "bidirectional"))
    )
    (net (code "98") (name "unconnected-(U$7-PadP$50)") (class "Default")
      (node (ref "U$7") (pin "P$50") (pinfunction "P$50_P$50") (pintype "bidirectional"))
    )
    (net (code "99") (name "unconnected-(U$7-PadP$54)") (class "Default")
      (node (ref "U$7") (pin "P$54") (pinfunction "P$54_P$54") (pintype "bidirectional"))
    )
    (net (code "100") (name "unconnected-(U$7-PadP$58)") (class "Default")
      (node (ref "U$7") (pin "P$58") (pinfunction "P$58_P$58") (pintype "bidirectional"))
    )
    (net (code "101") (name "unconnected-(U$7-PadP$60)") (class "Default")
      (node (ref "U$7") (pin "P$60") (pinfunction "P$60_P$60") (pintype "bidirectional"))
    )
    (net (code "102") (name "unconnected-(U$7-PadP$61)") (class "Default")
      (node (ref "U$7") (pin "P$61") (pinfunction "P$61_P$61") (pintype "bidirectional"))
    )
    (net (code "103") (name "unconnected-(U$7-PadP$62)") (class "Default")
      (node (ref "U$7") (pin "P$62") (pinfunction "P$62_P$62") (pintype "bidirectional"))
    )
    (net (code "104") (name "unconnected-(U$7-PadP$63)") (class "Default")
      (node (ref "U$7") (pin "P$63") (pinfunction "P$63_P$63") (pintype "bidirectional"))
    )
    (net (code "105") (name "unconnected-(U$7-PadP$64)") (class "Default")
      (node (ref "U$7") (pin "P$64") (pinfunction "P$64_P$64") (pintype "bidirectional"))
    )
    (net (code "106") (name "unconnected-(U$7-PadP$65)") (class "Default")
      (node (ref "U$7") (pin "P$65") (pinfunction "P$65_P$65") (pintype "bidirectional"))
    )
    (net (code "107") (name "unconnected-(U$7-PadP$66)") (class "Default")
      (node (ref "U$7") (pin "P$66") (pinfunction "P$66_P$66") (pintype "bidirectional"))
    )
    (net (code "108") (name "unconnected-(U$7-PadP$67)") (class "Default")
      (node (ref "U$7") (pin "P$67") (pinfunction "P$67_P$67") (pintype "bidirectional"))
    )
    (net (code "109") (name "unconnected-(U$7-PadP$68)") (class "Default")
      (node (ref "U$7") (pin "P$68") (pinfunction "P$68_P$68") (pintype "bidirectional"))
    )
    (net (code "110") (name "unconnected-(U$7-PadP$89)") (class "Default")
      (node (ref "U$7") (pin "P$89") (pinfunction "P$89_P$89") (pintype "bidirectional"))
    )
    (net (code "111") (name "unconnected-(U$7-PadP$90)") (class "Default")
      (node (ref "U$7") (pin "P$90") (pinfunction "P$90_P$90") (pintype "bidirectional"))
    )
    (net (code "112") (name "unconnected-(U$7-PadP$91)") (class "Default")
      (node (ref "U$7") (pin "P$91") (pinfunction "P$91_P$91") (pintype "bidirectional"))
    )
    (net (code "113") (name "unconnected-(U$7-PadP$92)") (class "Default")
      (node (ref "U$7") (pin "P$92") (pinfunction "P$92_P$92") (pintype "bidirectional"))
    )
    (net (code "114") (name "unconnected-(U$7-PadP$95)") (class "Default")
      (node (ref "U$7") (pin "P$95") (pinfunction "P$95_P$95") (pintype "bidirectional"))
    )
    (net (code "115") (name "unconnected-(U$7-PadP$96)") (class "Default")
      (node (ref "U$7") (pin "P$96") (pinfunction "P$96_P$96") (pintype "bidirectional"))
    )
    (net (code "116") (name "unconnected-(U$7-RAHS_GND-PadP$94)") (class "Default")
      (node (ref "U$7") (pin "P$94") (pinfunction "RAHS_GND_P$94") (pintype "bidirectional"))
    )
    (net (code "117") (name "unconnected-(U$7-RAHS_VBAT-PadP$93)") (class "Default")
      (node (ref "U$7") (pin "P$93") (pinfunction "RAHS_VBAT_P$93") (pintype "bidirectional"))
    )
    (net (code "118") (name "unconnected-(U$9-BDOT_3.3V-PadP$83)") (class "Default")
      (node (ref "U$9") (pin "P$83") (pinfunction "BDOT_3.3V_P$83") (pintype "bidirectional"))
    )
    (net (code "119") (name "unconnected-(U$9-BDOT_3.3V-PadP$84)") (class "Default")
      (node (ref "U$9") (pin "P$84") (pinfunction "BDOT_3.3V_P$84") (pintype "bidirectional"))
    )
    (net (code "120") (name "unconnected-(U$9-BDOT_5V-PadP$81)") (class "Default")
      (node (ref "U$9") (pin "P$81") (pinfunction "BDOT_5V_P$81") (pintype "bidirectional"))
    )
    (net (code "121") (name "unconnected-(U$9-BDOT_5V-PadP$82)") (class "Default")
      (node (ref "U$9") (pin "P$82") (pinfunction "BDOT_5V_P$82") (pintype "bidirectional"))
    )
    (net (code "122") (name "unconnected-(U$9-COM1_GND-PadP$102)") (class "Default")
      (node (ref "U$9") (pin "P$102") (pinfunction "COM1_GND_P$102") (pintype "bidirectional"))
    )
    (net (code "123") (name "unconnected-(U$9-COM1_GND-PadP$104)") (class "Default")
      (node (ref "U$9") (pin "P$104") (pinfunction "COM1_GND_P$104") (pintype "bidirectional"))
    )
    (net (code "124") (name "unconnected-(U$9-COM1_VBAT-PadP$101)") (class "Default")
      (node (ref "U$9") (pin "P$101") (pinfunction "COM1_VBAT_P$101") (pintype "bidirectional"))
    )
    (net (code "125") (name "unconnected-(U$9-COM1_VBAT-PadP$103)") (class "Default")
      (node (ref "U$9") (pin "P$103") (pinfunction "COM1_VBAT_P$103") (pintype "bidirectional"))
    )
    (net (code "126") (name "unconnected-(U$9-COM2_GND-PadP$98)") (class "Default")
      (node (ref "U$9") (pin "P$98") (pinfunction "COM2_GND_P$98") (pintype "bidirectional"))
    )
    (net (code "127") (name "unconnected-(U$9-COM2_GND-PadP$100)") (class "Default")
      (node (ref "U$9") (pin "P$100") (pinfunction "COM2_GND_P$100") (pintype "bidirectional"))
    )
    (net (code "128") (name "unconnected-(U$9-COM2_VBAT-PadP$97)") (class "Default")
      (node (ref "U$9") (pin "P$97") (pinfunction "COM2_VBAT_P$97") (pintype "bidirectional"))
    )
    (net (code "129") (name "unconnected-(U$9-COM2_VBAT-PadP$99)") (class "Default")
      (node (ref "U$9") (pin "P$99") (pinfunction "COM2_VBAT_P$99") (pintype "bidirectional"))
    )
    (net (code "130") (name "unconnected-(U$9-ESTIMAT_3.3V-PadP$75)") (class "Default")
      (node (ref "U$9") (pin "P$75") (pinfunction "ESTIMAT_3.3V_P$75") (pintype "bidirectional"))
    )
    (net (code "131") (name "unconnected-(U$9-ESTIMAT_3.3V-PadP$76)") (class "Default")
      (node (ref "U$9") (pin "P$76") (pinfunction "ESTIMAT_3.3V_P$76") (pintype "bidirectional"))
    )
    (net (code "132") (name "unconnected-(U$9-ESTIMAT_5V-PadP$73)") (class "Default")
      (node (ref "U$9") (pin "P$73") (pinfunction "ESTIMAT_5V_P$73") (pintype "bidirectional"))
    )
    (net (code "133") (name "unconnected-(U$9-ESTIMAT_5V-PadP$74)") (class "Default")
      (node (ref "U$9") (pin "P$74") (pinfunction "ESTIMAT_5V_P$74") (pintype "bidirectional"))
    )
    (net (code "134") (name "unconnected-(U$9-P-PadP$59)") (class "Default")
      (node (ref "U$9") (pin "P$59") (pinfunction "P_P$59") (pintype "bidirectional"))
    )
    (net (code "135") (name "unconnected-(U$9-PadP$37)") (class "Default")
      (node (ref "U$9") (pin "P$37") (pinfunction "P$37_P$37") (pintype "bidirectional"))
    )
    (net (code "136") (name "unconnected-(U$9-PadP$38)") (class "Default")
      (node (ref "U$9") (pin "P$38") (pinfunction "P$38_P$38") (pintype "bidirectional"))
    )
    (net (code "137") (name "unconnected-(U$9-PadP$39)") (class "Default")
      (node (ref "U$9") (pin "P$39") (pinfunction "P$39_P$39") (pintype "bidirectional"))
    )
    (net (code "138") (name "unconnected-(U$9-PadP$40)") (class "Default")
      (node (ref "U$9") (pin "P$40") (pinfunction "P$40_P$40") (pintype "bidirectional"))
    )
    (net (code "139") (name "unconnected-(U$9-PadP$41)") (class "Default")
      (node (ref "U$9") (pin "P$41") (pinfunction "P$41_P$41") (pintype "bidirectional"))
    )
    (net (code "140") (name "unconnected-(U$9-PadP$42)") (class "Default")
      (node (ref "U$9") (pin "P$42") (pinfunction "P$42_P$42") (pintype "bidirectional"))
    )
    (net (code "141") (name "unconnected-(U$9-PadP$43)") (class "Default")
      (node (ref "U$9") (pin "P$43") (pinfunction "P$43_P$43") (pintype "bidirectional"))
    )
    (net (code "142") (name "unconnected-(U$9-PadP$44)") (class "Default")
      (node (ref "U$9") (pin "P$44") (pinfunction "P$44_P$44") (pintype "bidirectional"))
    )
    (net (code "143") (name "unconnected-(U$9-PadP$46)") (class "Default")
      (node (ref "U$9") (pin "P$46") (pinfunction "P$46_P$46") (pintype "bidirectional"))
    )
    (net (code "144") (name "unconnected-(U$9-PadP$47)") (class "Default")
      (node (ref "U$9") (pin "P$47") (pinfunction "P$47_P$47") (pintype "bidirectional"))
    )
    (net (code "145") (name "unconnected-(U$9-PadP$48)") (class "Default")
      (node (ref "U$9") (pin "P$48") (pinfunction "P$48_P$48") (pintype "bidirectional"))
    )
    (net (code "146") (name "unconnected-(U$9-PadP$50)") (class "Default")
      (node (ref "U$9") (pin "P$50") (pinfunction "P$50_P$50") (pintype "bidirectional"))
    )
    (net (code "147") (name "unconnected-(U$9-PadP$54)") (class "Default")
      (node (ref "U$9") (pin "P$54") (pinfunction "P$54_P$54") (pintype "bidirectional"))
    )
    (net (code "148") (name "unconnected-(U$9-PadP$58)") (class "Default")
      (node (ref "U$9") (pin "P$58") (pinfunction "P$58_P$58") (pintype "bidirectional"))
    )
    (net (code "149") (name "unconnected-(U$9-PadP$60)") (class "Default")
      (node (ref "U$9") (pin "P$60") (pinfunction "P$60_P$60") (pintype "bidirectional"))
    )
    (net (code "150") (name "unconnected-(U$9-PadP$61)") (class "Default")
      (node (ref "U$9") (pin "P$61") (pinfunction "P$61_P$61") (pintype "bidirectional"))
    )
    (net (code "151") (name "unconnected-(U$9-PadP$62)") (class "Default")
      (node (ref "U$9") (pin "P$62") (pinfunction "P$62_P$62") (pintype "bidirectional"))
    )
    (net (code "152") (name "unconnected-(U$9-PadP$63)") (class "Default")
      (node (ref "U$9") (pin "P$63") (pinfunction "P$63_P$63") (pintype "bidirectional"))
    )
    (net (code "153") (name "unconnected-(U$9-PadP$64)") (class "Default")
      (node (ref "U$9") (pin "P$64") (pinfunction "P$64_P$64") (pintype "bidirectional"))
    )
    (net (code "154") (name "unconnected-(U$9-PadP$65)") (class "Default")
      (node (ref "U$9") (pin "P$65") (pinfunction "P$65_P$65") (pintype "bidirectional"))
    )
    (net (code "155") (name "unconnected-(U$9-PadP$66)") (class "Default")
      (node (ref "U$9") (pin "P$66") (pinfunction "P$66_P$66") (pintype "bidirectional"))
    )
    (net (code "156") (name "unconnected-(U$9-PadP$67)") (class "Default")
      (node (ref "U$9") (pin "P$67") (pinfunction "P$67_P$67") (pintype "bidirectional"))
    )
    (net (code "157") (name "unconnected-(U$9-PadP$68)") (class "Default")
      (node (ref "U$9") (pin "P$68") (pinfunction "P$68_P$68") (pintype "bidirectional"))
    )
    (net (code "158") (name "unconnected-(U$9-PadP$89)") (class "Default")
      (node (ref "U$9") (pin "P$89") (pinfunction "P$89_P$89") (pintype "bidirectional"))
    )
    (net (code "159") (name "unconnected-(U$9-PadP$90)") (class "Default")
      (node (ref "U$9") (pin "P$90") (pinfunction "P$90_P$90") (pintype "bidirectional"))
    )
    (net (code "160") (name "unconnected-(U$9-PadP$91)") (class "Default")
      (node (ref "U$9") (pin "P$91") (pinfunction "P$91_P$91") (pintype "bidirectional"))
    )
    (net (code "161") (name "unconnected-(U$9-PadP$92)") (class "Default")
      (node (ref "U$9") (pin "P$92") (pinfunction "P$92_P$92") (pintype "bidirectional"))
    )
    (net (code "162") (name "unconnected-(U$9-PadP$95)") (class "Default")
      (node (ref "U$9") (pin "P$95") (pinfunction "P$95_P$95") (pintype "bidirectional"))
    )
    (net (code "163") (name "unconnected-(U$9-PadP$96)") (class "Default")
      (node (ref "U$9") (pin "P$96") (pinfunction "P$96_P$96") (pintype "bidirectional"))
    )
    (net (code "164") (name "unconnected-(U$9-RAHS_GND-PadP$94)") (class "Default")
      (node (ref "U$9") (pin "P$94") (pinfunction "RAHS_GND_P$94") (pintype "bidirectional"))
    )
    (net (code "165") (name "unconnected-(U$9-RAHS_VBAT-PadP$93)") (class "Default")
      (node (ref "U$9") (pin "P$93") (pinfunction "RAHS_VBAT_P$93") (pintype "bidirectional"))
    )
    (net (code "166") (name "unconnected-(U$10-Pad14)") (class "Default")
      (node (ref "U$10") (pin "14") (pinfunction "14_14") (pintype "passive"))
    )
    (net (code "167") (name "unconnected-(U$10-Pad15)") (class "Default")
      (node (ref "U$10") (pin "15") (pinfunction "15_15") (pintype "passive"))
    )
    (net (code "168") (name "unconnected-(U$10-Pad18)") (class "Default")
      (node (ref "U$10") (pin "18") (pinfunction "18_18") (pintype "passive"))
    )
    (net (code "169") (name "unconnected-(U$10-Pad19)") (class "Default")
      (node (ref "U$10") (pin "19") (pinfunction "19_19") (pintype "passive"))
    )
    (net (code "170") (name "unconnected-(U$10-Pad20)") (class "Default")
      (node (ref "U$10") (pin "20") (pinfunction "20_20") (pintype "passive"))
    )
    (net (code "171") (name "unconnected-(U$11-BDOT_3.3V-PadP$83)") (class "Default")
      (node (ref "U$11") (pin "P$83") (pinfunction "BDOT_3.3V_P$83") (pintype "bidirectional"))
    )
    (net (code "172") (name "unconnected-(U$11-BDOT_3.3V-PadP$84)") (class "Default")
      (node (ref "U$11") (pin "P$84") (pinfunction "BDOT_3.3V_P$84") (pintype "bidirectional"))
    )
    (net (code "173") (name "unconnected-(U$11-BDOT_5V-PadP$81)") (class "Default")
      (node (ref "U$11") (pin "P$81") (pinfunction "BDOT_5V_P$81") (pintype "bidirectional"))
    )
    (net (code "174") (name "unconnected-(U$11-BDOT_5V-PadP$82)") (class "Default")
      (node (ref "U$11") (pin "P$82") (pinfunction "BDOT_5V_P$82") (pintype "bidirectional"))
    )
    (net (code "175") (name "unconnected-(U$11-COM1_GND-PadP$102)") (class "Default")
      (node (ref "U$11") (pin "P$102") (pinfunction "COM1_GND_P$102") (pintype "bidirectional"))
    )
    (net (code "176") (name "unconnected-(U$11-COM1_GND-PadP$104)") (class "Default")
      (node (ref "U$11") (pin "P$104") (pinfunction "COM1_GND_P$104") (pintype "bidirectional"))
    )
    (net (code "177") (name "unconnected-(U$11-COM1_VBAT-PadP$101)") (class "Default")
      (node (ref "U$11") (pin "P$101") (pinfunction "COM1_VBAT_P$101") (pintype "bidirectional"))
    )
    (net (code "178") (name "unconnected-(U$11-COM1_VBAT-PadP$103)") (class "Default")
      (node (ref "U$11") (pin "P$103") (pinfunction "COM1_VBAT_P$103") (pintype "bidirectional"))
    )
    (net (code "179") (name "unconnected-(U$11-COM2_GND-PadP$98)") (class "Default")
      (node (ref "U$11") (pin "P$98") (pinfunction "COM2_GND_P$98") (pintype "bidirectional"))
    )
    (net (code "180") (name "unconnected-(U$11-COM2_GND-PadP$100)") (class "Default")
      (node (ref "U$11") (pin "P$100") (pinfunction "COM2_GND_P$100") (pintype "bidirectional"))
    )
    (net (code "181") (name "unconnected-(U$11-COM2_VBAT-PadP$97)") (class "Default")
      (node (ref "U$11") (pin "P$97") (pinfunction "COM2_VBAT_P$97") (pintype "bidirectional"))
    )
    (net (code "182") (name "unconnected-(U$11-COM2_VBAT-PadP$99)") (class "Default")
      (node (ref "U$11") (pin "P$99") (pinfunction "COM2_VBAT_P$99") (pintype "bidirectional"))
    )
    (net (code "183") (name "unconnected-(U$11-ESTIMAT_3.3V-PadP$75)") (class "Default")
      (node (ref "U$11") (pin "P$75") (pinfunction "ESTIMAT_3.3V_P$75") (pintype "bidirectional"))
    )
    (net (code "184") (name "unconnected-(U$11-ESTIMAT_3.3V-PadP$76)") (class "Default")
      (node (ref "U$11") (pin "P$76") (pinfunction "ESTIMAT_3.3V_P$76") (pintype "bidirectional"))
    )
    (net (code "185") (name "unconnected-(U$11-ESTIMAT_5V-PadP$73)") (class "Default")
      (node (ref "U$11") (pin "P$73") (pinfunction "ESTIMAT_5V_P$73") (pintype "bidirectional"))
    )
    (net (code "186") (name "unconnected-(U$11-ESTIMAT_5V-PadP$74)") (class "Default")
      (node (ref "U$11") (pin "P$74") (pinfunction "ESTIMAT_5V_P$74") (pintype "bidirectional"))
    )
    (net (code "187") (name "unconnected-(U$11-P-PadP$59)") (class "Default")
      (node (ref "U$11") (pin "P$59") (pinfunction "P_P$59") (pintype "bidirectional"))
    )
    (net (code "188") (name "unconnected-(U$11-PadP$37)") (class "Default")
      (node (ref "U$11") (pin "P$37") (pinfunction "P$37_P$37") (pintype "bidirectional"))
    )
    (net (code "189") (name "unconnected-(U$11-PadP$38)") (class "Default")
      (node (ref "U$11") (pin "P$38") (pinfunction "P$38_P$38") (pintype "bidirectional"))
    )
    (net (code "190") (name "unconnected-(U$11-PadP$39)") (class "Default")
      (node (ref "U$11") (pin "P$39") (pinfunction "P$39_P$39") (pintype "bidirectional"))
    )
    (net (code "191") (name "unconnected-(U$11-PadP$40)") (class "Default")
      (node (ref "U$11") (pin "P$40") (pinfunction "P$40_P$40") (pintype "bidirectional"))
    )
    (net (code "192") (name "unconnected-(U$11-PadP$41)") (class "Default")
      (node (ref "U$11") (pin "P$41") (pinfunction "P$41_P$41") (pintype "bidirectional"))
    )
    (net (code "193") (name "unconnected-(U$11-PadP$42)") (class "Default")
      (node (ref "U$11") (pin "P$42") (pinfunction "P$42_P$42") (pintype "bidirectional"))
    )
    (net (code "194") (name "unconnected-(U$11-PadP$43)") (class "Default")
      (node (ref "U$11") (pin "P$43") (pinfunction "P$43_P$43") (pintype "bidirectional"))
    )
    (net (code "195") (name "unconnected-(U$11-PadP$44)") (class "Default")
      (node (ref "U$11") (pin "P$44") (pinfunction "P$44_P$44") (pintype "bidirectional"))
    )
    (net (code "196") (name "unconnected-(U$11-PadP$46)") (class "Default")
      (node (ref "U$11") (pin "P$46") (pinfunction "P$46_P$46") (pintype "bidirectional"))
    )
    (net (code "197") (name "unconnected-(U$11-PadP$47)") (class "Default")
      (node (ref "U$11") (pin "P$47") (pinfunction "P$47_P$47") (pintype "bidirectional"))
    )
    (net (code "198") (name "unconnected-(U$11-PadP$48)") (class "Default")
      (node (ref "U$11") (pin "P$48") (pinfunction "P$48_P$48") (pintype "bidirectional"))
    )
    (net (code "199") (name "unconnected-(U$11-PadP$50)") (class "Default")
      (node (ref "U$11") (pin "P$50") (pinfunction "P$50_P$50") (pintype "bidirectional"))
    )
    (net (code "200") (name "unconnected-(U$11-PadP$54)") (class "Default")
      (node (ref "U$11") (pin "P$54") (pinfunction "P$54_P$54") (pintype "bidirectional"))
    )
    (net (code "201") (name "unconnected-(U$11-PadP$58)") (class "Default")
      (node (ref "U$11") (pin "P$58") (pinfunction "P$58_P$58") (pintype "bidirectional"))
    )
    (net (code "202") (name "unconnected-(U$11-PadP$60)") (class "Default")
      (node (ref "U$11") (pin "P$60") (pinfunction "P$60_P$60") (pintype "bidirectional"))
    )
    (net (code "203") (name "unconnected-(U$11-PadP$61)") (class "Default")
      (node (ref "U$11") (pin "P$61") (pinfunction "P$61_P$61") (pintype "bidirectional"))
    )
    (net (code "204") (name "unconnected-(U$11-PadP$62)") (class "Default")
      (node (ref "U$11") (pin "P$62") (pinfunction "P$62_P$62") (pintype "bidirectional"))
    )
    (net (code "205") (name "unconnected-(U$11-PadP$63)") (class "Default")
      (node (ref "U$11") (pin "P$63") (pinfunction "P$63_P$63") (pintype "bidirectional"))
    )
    (net (code "206") (name "unconnected-(U$11-PadP$64)") (class "Default")
      (node (ref "U$11") (pin "P$64") (pinfunction "P$64_P$64") (pintype "bidirectional"))
    )
    (net (code "207") (name "unconnected-(U$11-PadP$65)") (class "Default")
      (node (ref "U$11") (pin "P$65") (pinfunction "P$65_P$65") (pintype "bidirectional"))
    )
    (net (code "208") (name "unconnected-(U$11-PadP$66)") (class "Default")
      (node (ref "U$11") (pin "P$66") (pinfunction "P$66_P$66") (pintype "bidirectional"))
    )
    (net (code "209") (name "unconnected-(U$11-PadP$67)") (class "Default")
      (node (ref "U$11") (pin "P$67") (pinfunction "P$67_P$67") (pintype "bidirectional"))
    )
    (net (code "210") (name "unconnected-(U$11-PadP$68)") (class "Default")
      (node (ref "U$11") (pin "P$68") (pinfunction "P$68_P$68") (pintype "bidirectional"))
    )
    (net (code "211") (name "unconnected-(U$11-PadP$89)") (class "Default")
      (node (ref "U$11") (pin "P$89") (pinfunction "P$89_P$89") (pintype "bidirectional"))
    )
    (net (code "212") (name "unconnected-(U$11-PadP$90)") (class "Default")
      (node (ref "U$11") (pin "P$90") (pinfunction "P$90_P$90") (pintype "bidirectional"))
    )
    (net (code "213") (name "unconnected-(U$11-PadP$91)") (class "Default")
      (node (ref "U$11") (pin "P$91") (pinfunction "P$91_P$91") (pintype "bidirectional"))
    )
    (net (code "214") (name "unconnected-(U$11-PadP$92)") (class "Default")
      (node (ref "U$11") (pin "P$92") (pinfunction "P$92_P$92") (pintype "bidirectional"))
    )
    (net (code "215") (name "unconnected-(U$11-PadP$95)") (class "Default")
      (node (ref "U$11") (pin "P$95") (pinfunction "P$95_P$95") (pintype "bidirectional"))
    )
    (net (code "216") (name "unconnected-(U$11-PadP$96)") (class "Default")
      (node (ref "U$11") (pin "P$96") (pinfunction "P$96_P$96") (pintype "bidirectional"))
    )
    (net (code "217") (name "unconnected-(U$11-RAHS_GND-PadP$94)") (class "Default")
      (node (ref "U$11") (pin "P$94") (pinfunction "RAHS_GND_P$94") (pintype "bidirectional"))
    )
    (net (code "218") (name "unconnected-(U$11-RAHS_VBAT-PadP$93)") (class "Default")
      (node (ref "U$11") (pin "P$93") (pinfunction "RAHS_VBAT_P$93") (pintype "bidirectional"))
    )
    (net (code "219") (name "unconnected-(U$13-Pad14)") (class "Default")
      (node (ref "U$13") (pin "14") (pinfunction "14_14") (pintype "passive"))
    )
    (net (code "220") (name "unconnected-(U$13-Pad15)") (class "Default")
      (node (ref "U$13") (pin "15") (pinfunction "15_15") (pintype "passive"))
    )
    (net (code "221") (name "unconnected-(U$13-Pad18)") (class "Default")
      (node (ref "U$13") (pin "18") (pinfunction "18_18") (pintype "passive"))
    )
    (net (code "222") (name "unconnected-(U$13-Pad19)") (class "Default")
      (node (ref "U$13") (pin "19") (pinfunction "19_19") (pintype "passive"))
    )
    (net (code "223") (name "unconnected-(U$13-Pad20)") (class "Default")
      (node (ref "U$13") (pin "20") (pinfunction "20_20") (pintype "passive"))
    )
    (net (code "224") (name "unconnected-(U$17-Pad14)") (class "Default")
      (node (ref "U$17") (pin "14") (pinfunction "14_14") (pintype "passive"))
    )
    (net (code "225") (name "unconnected-(U$17-Pad15)") (class "Default")
      (node (ref "U$17") (pin "15") (pinfunction "15_15") (pintype "passive"))
    )
    (net (code "226") (name "unconnected-(U$17-Pad18)") (class "Default")
      (node (ref "U$17") (pin "18") (pinfunction "18_18") (pintype "passive"))
    )
    (net (code "227") (name "unconnected-(U$17-Pad19)") (class "Default")
      (node (ref "U$17") (pin "19") (pinfunction "19_19") (pintype "passive"))
    )
    (net (code "228") (name "unconnected-(U$17-Pad20)") (class "Default")
      (node (ref "U$17") (pin "20") (pinfunction "20_20") (pintype "passive"))
    )
    (net (code "229") (name "unconnected-(U$18-Pad14)") (class "Default")
      (node (ref "U$18") (pin "14") (pinfunction "14_14") (pintype "passive"))
    )
    (net (code "230") (name "unconnected-(U$18-Pad15)") (class "Default")
      (node (ref "U$18") (pin "15") (pinfunction "15_15") (pintype "passive"))
    )
    (net (code "231") (name "unconnected-(U$18-Pad18)") (class "Default")
      (node (ref "U$18") (pin "18") (pinfunction "18_18") (pintype "passive"))
    )
    (net (code "232") (name "unconnected-(U$18-Pad19)") (class "Default")
      (node (ref "U$18") (pin "19") (pinfunction "19_19") (pintype "passive"))
    )
    (net (code "233") (name "unconnected-(U$18-Pad20)") (class "Default")
      (node (ref "U$18") (pin "20") (pinfunction "20_20") (pintype "passive"))
    )
    (net (code "234") (name "unconnected-(U$19-Pad14)") (class "Default")
      (node (ref "U$19") (pin "14") (pinfunction "14_14") (pintype "passive"))
    )
    (net (code "235") (name "unconnected-(U$19-Pad15)") (class "Default")
      (node (ref "U$19") (pin "15") (pinfunction "15_15") (pintype "passive"))
    )
    (net (code "236") (name "unconnected-(U$19-Pad18)") (class "Default")
      (node (ref "U$19") (pin "18") (pinfunction "18_18") (pintype "passive"))
    )
    (net (code "237") (name "unconnected-(U$19-Pad19)") (class "Default")
      (node (ref "U$19") (pin "19") (pinfunction "19_19") (pintype "passive"))
    )
    (net (code "238") (name "unconnected-(U$19-Pad20)") (class "Default")
      (node (ref "U$19") (pin "20") (pinfunction "20_20") (pintype "passive"))
    )
  )
)
